# Keyboard.net
KiCad netlist of a schematic drawn in EAGLE
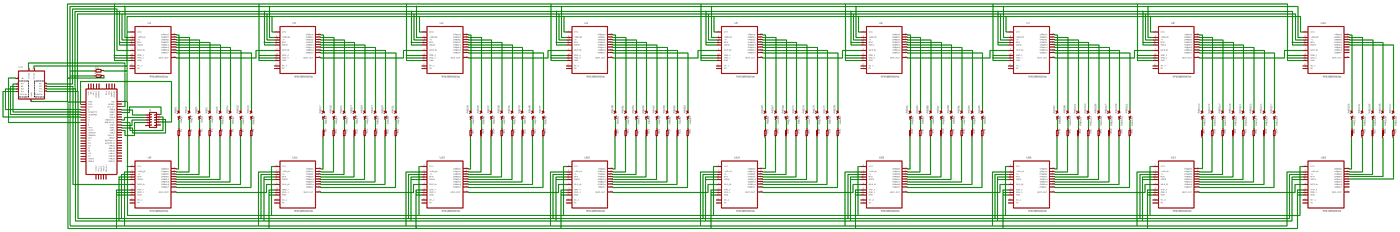
[diagram p0: schematic, sheet 1, overview]
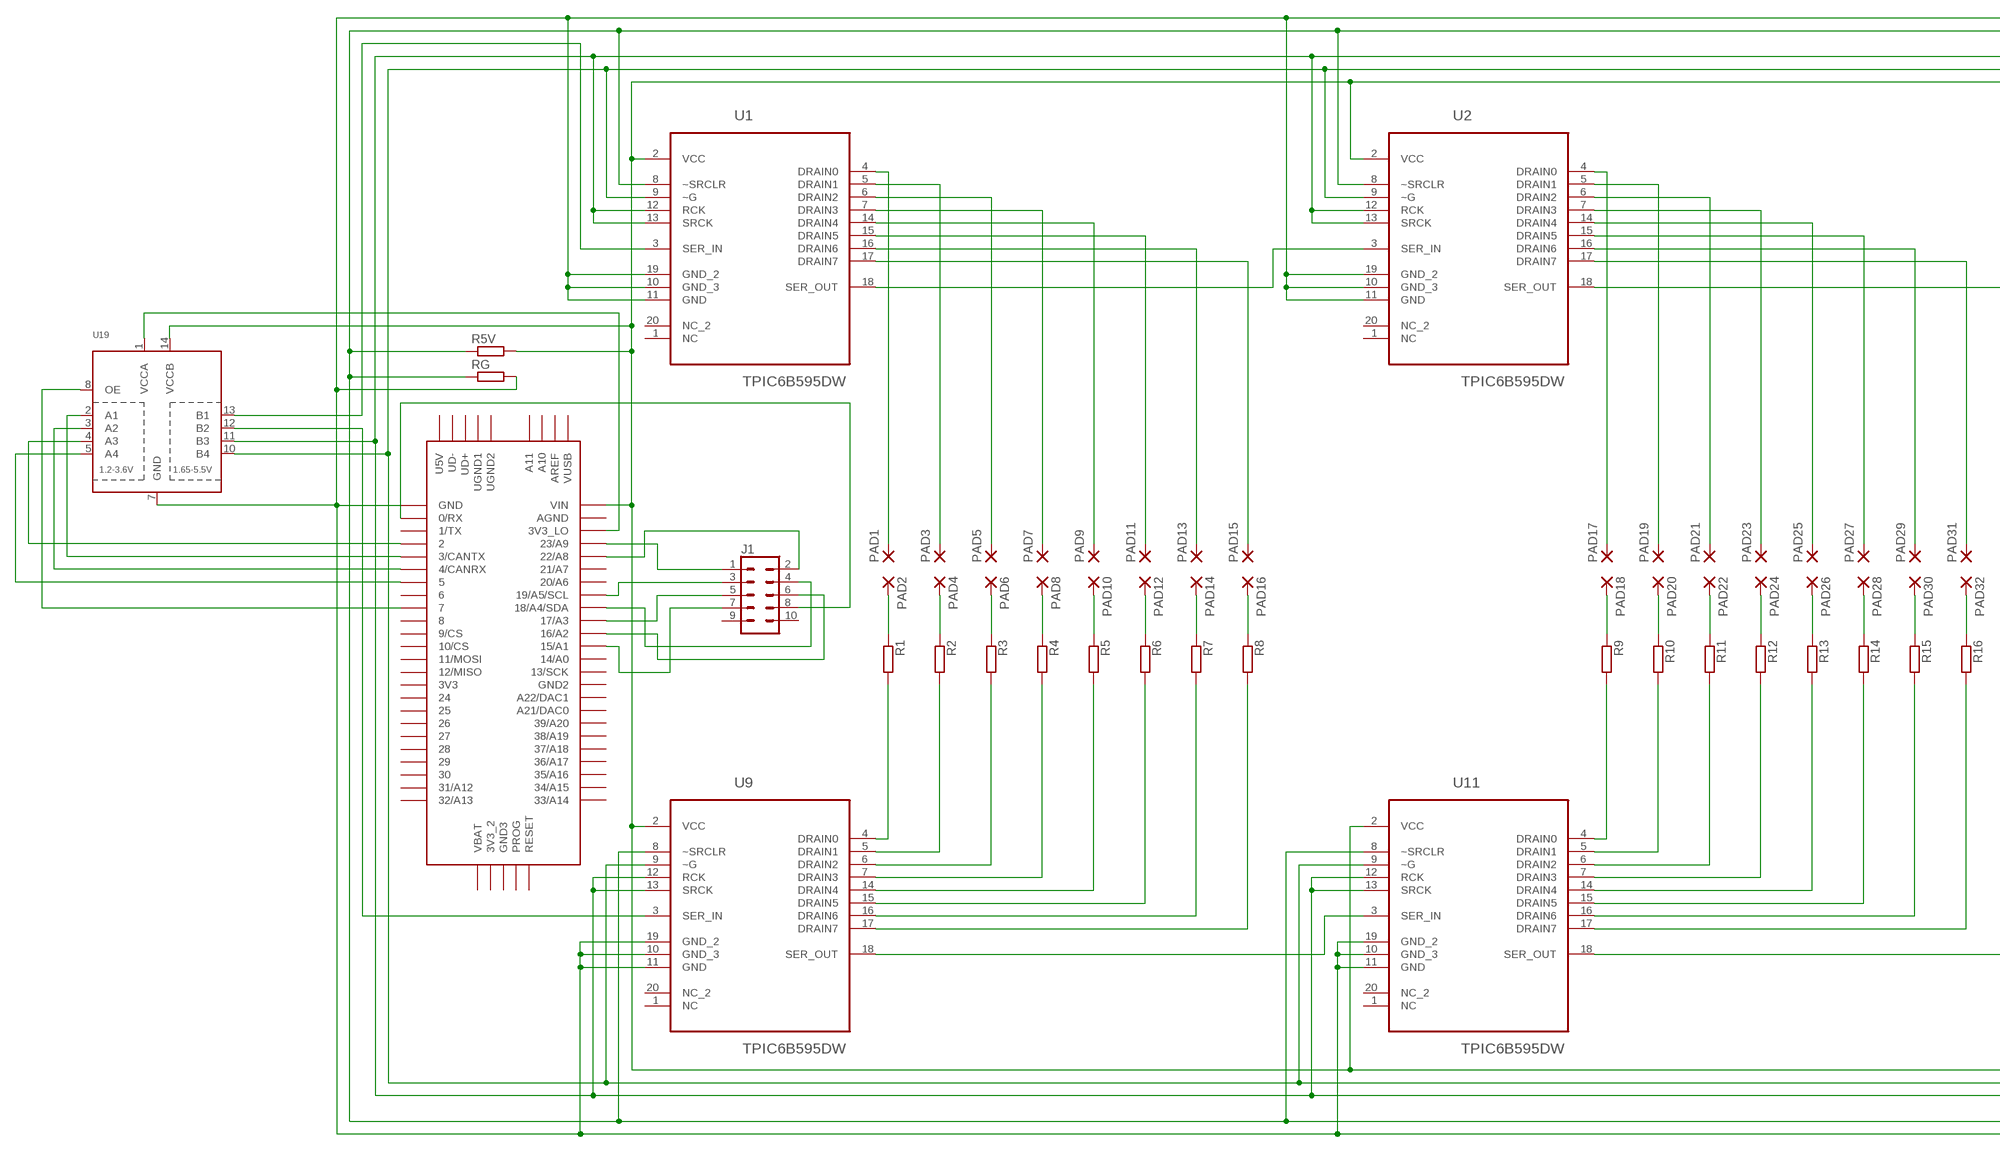
[diagram p1: schematic, sheet 1, part 1 of 4]
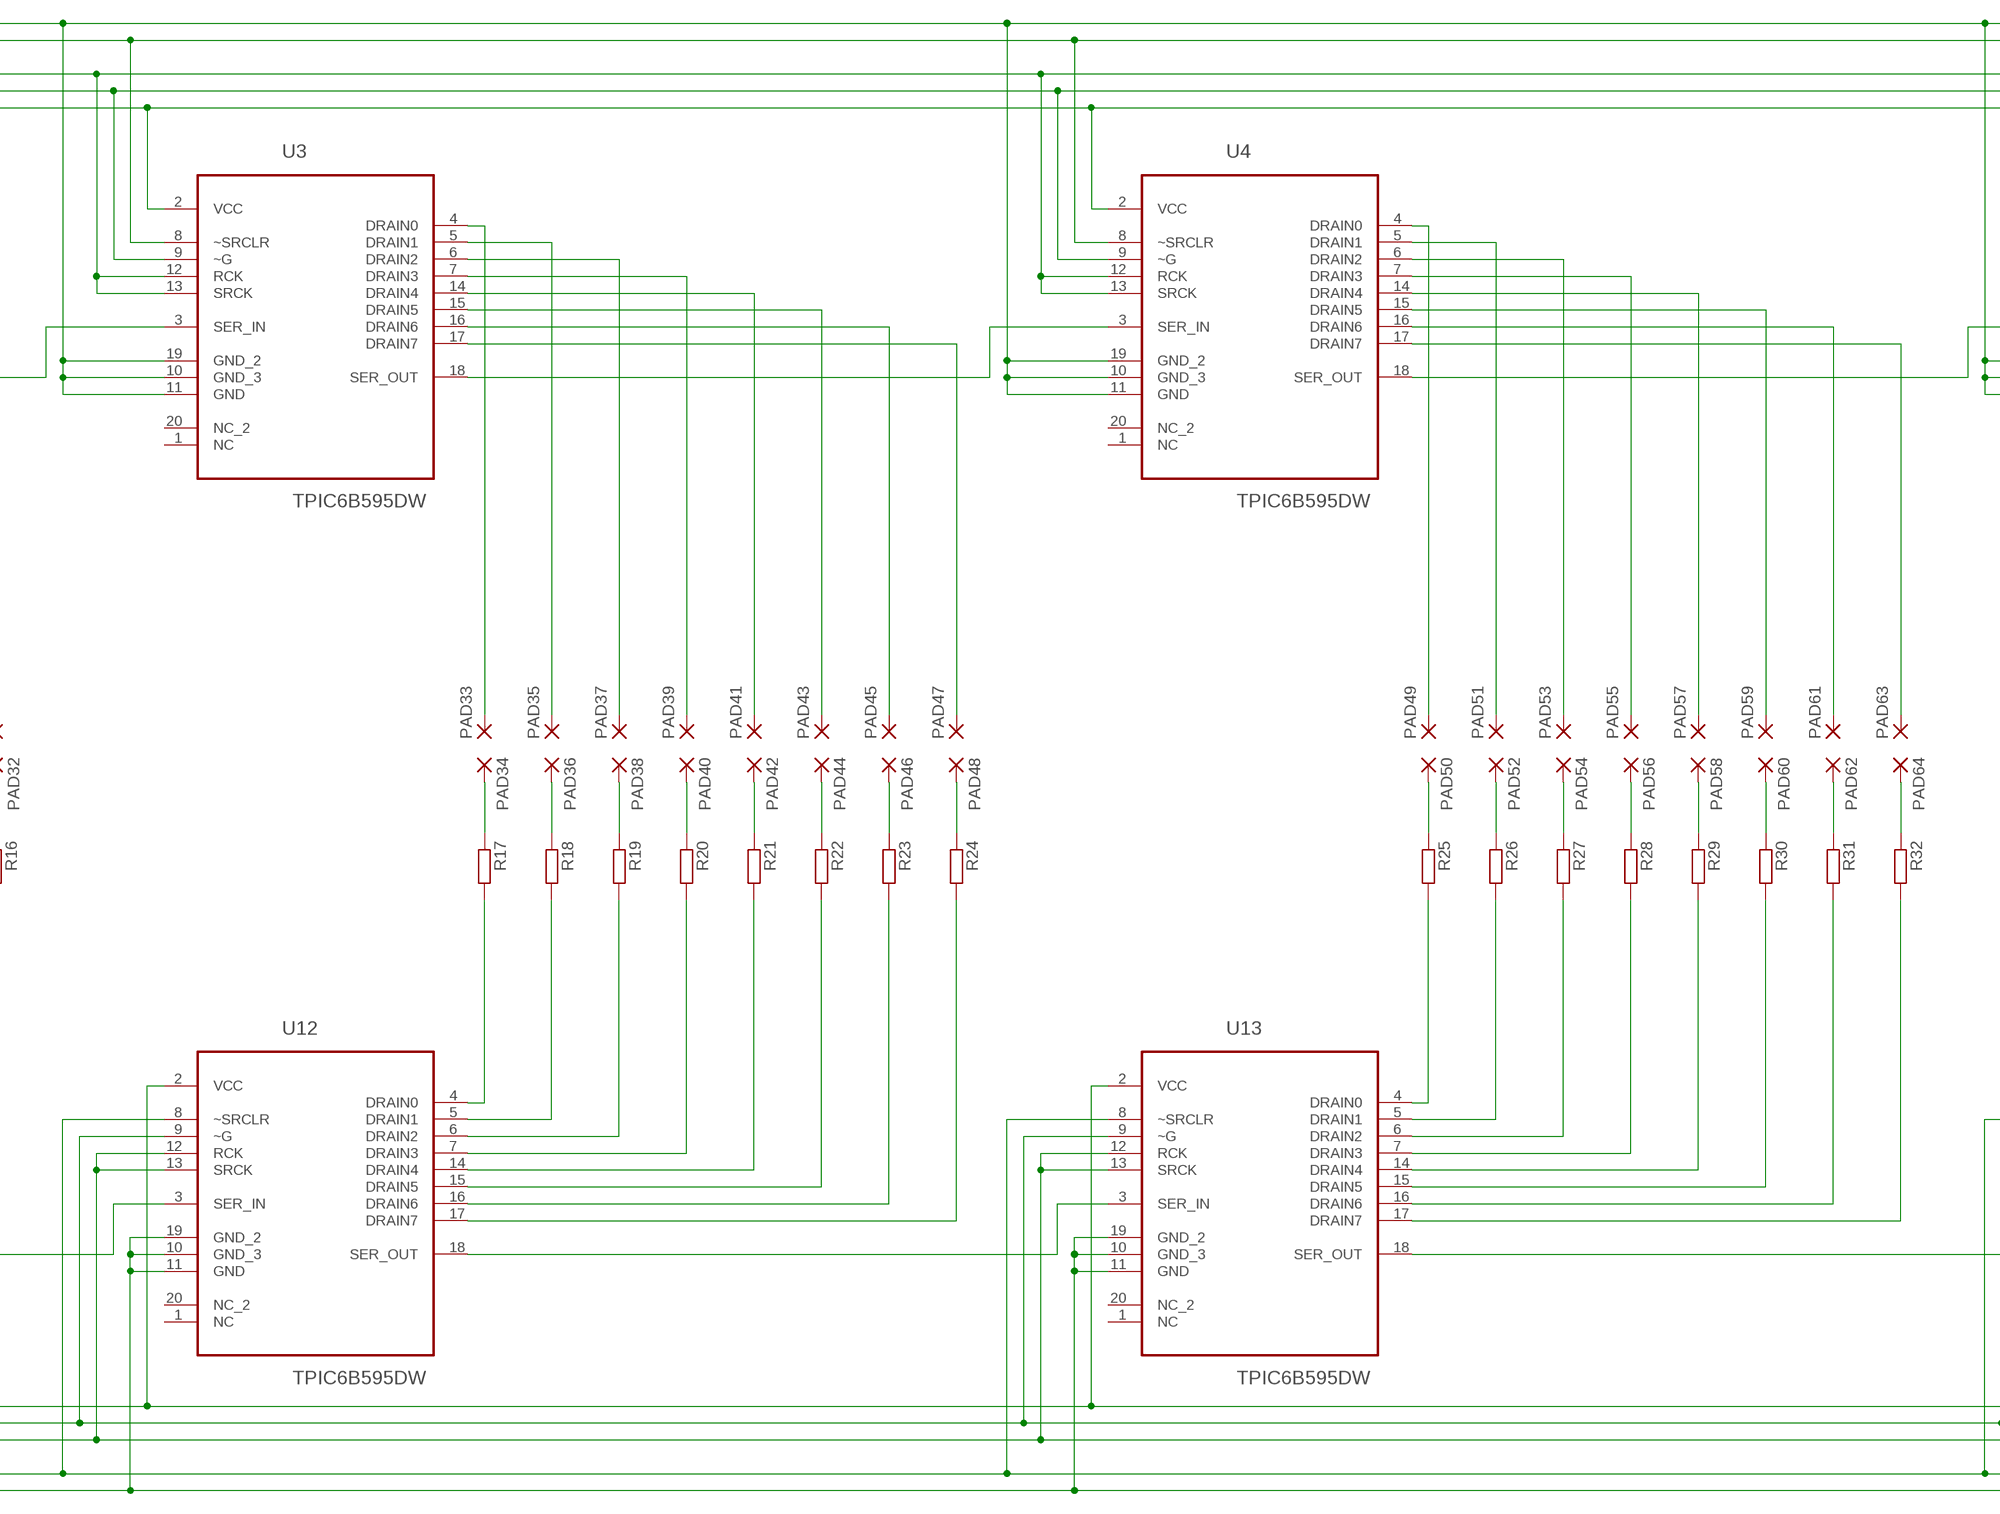
[diagram p2: schematic, sheet 1, part 2 of 4]
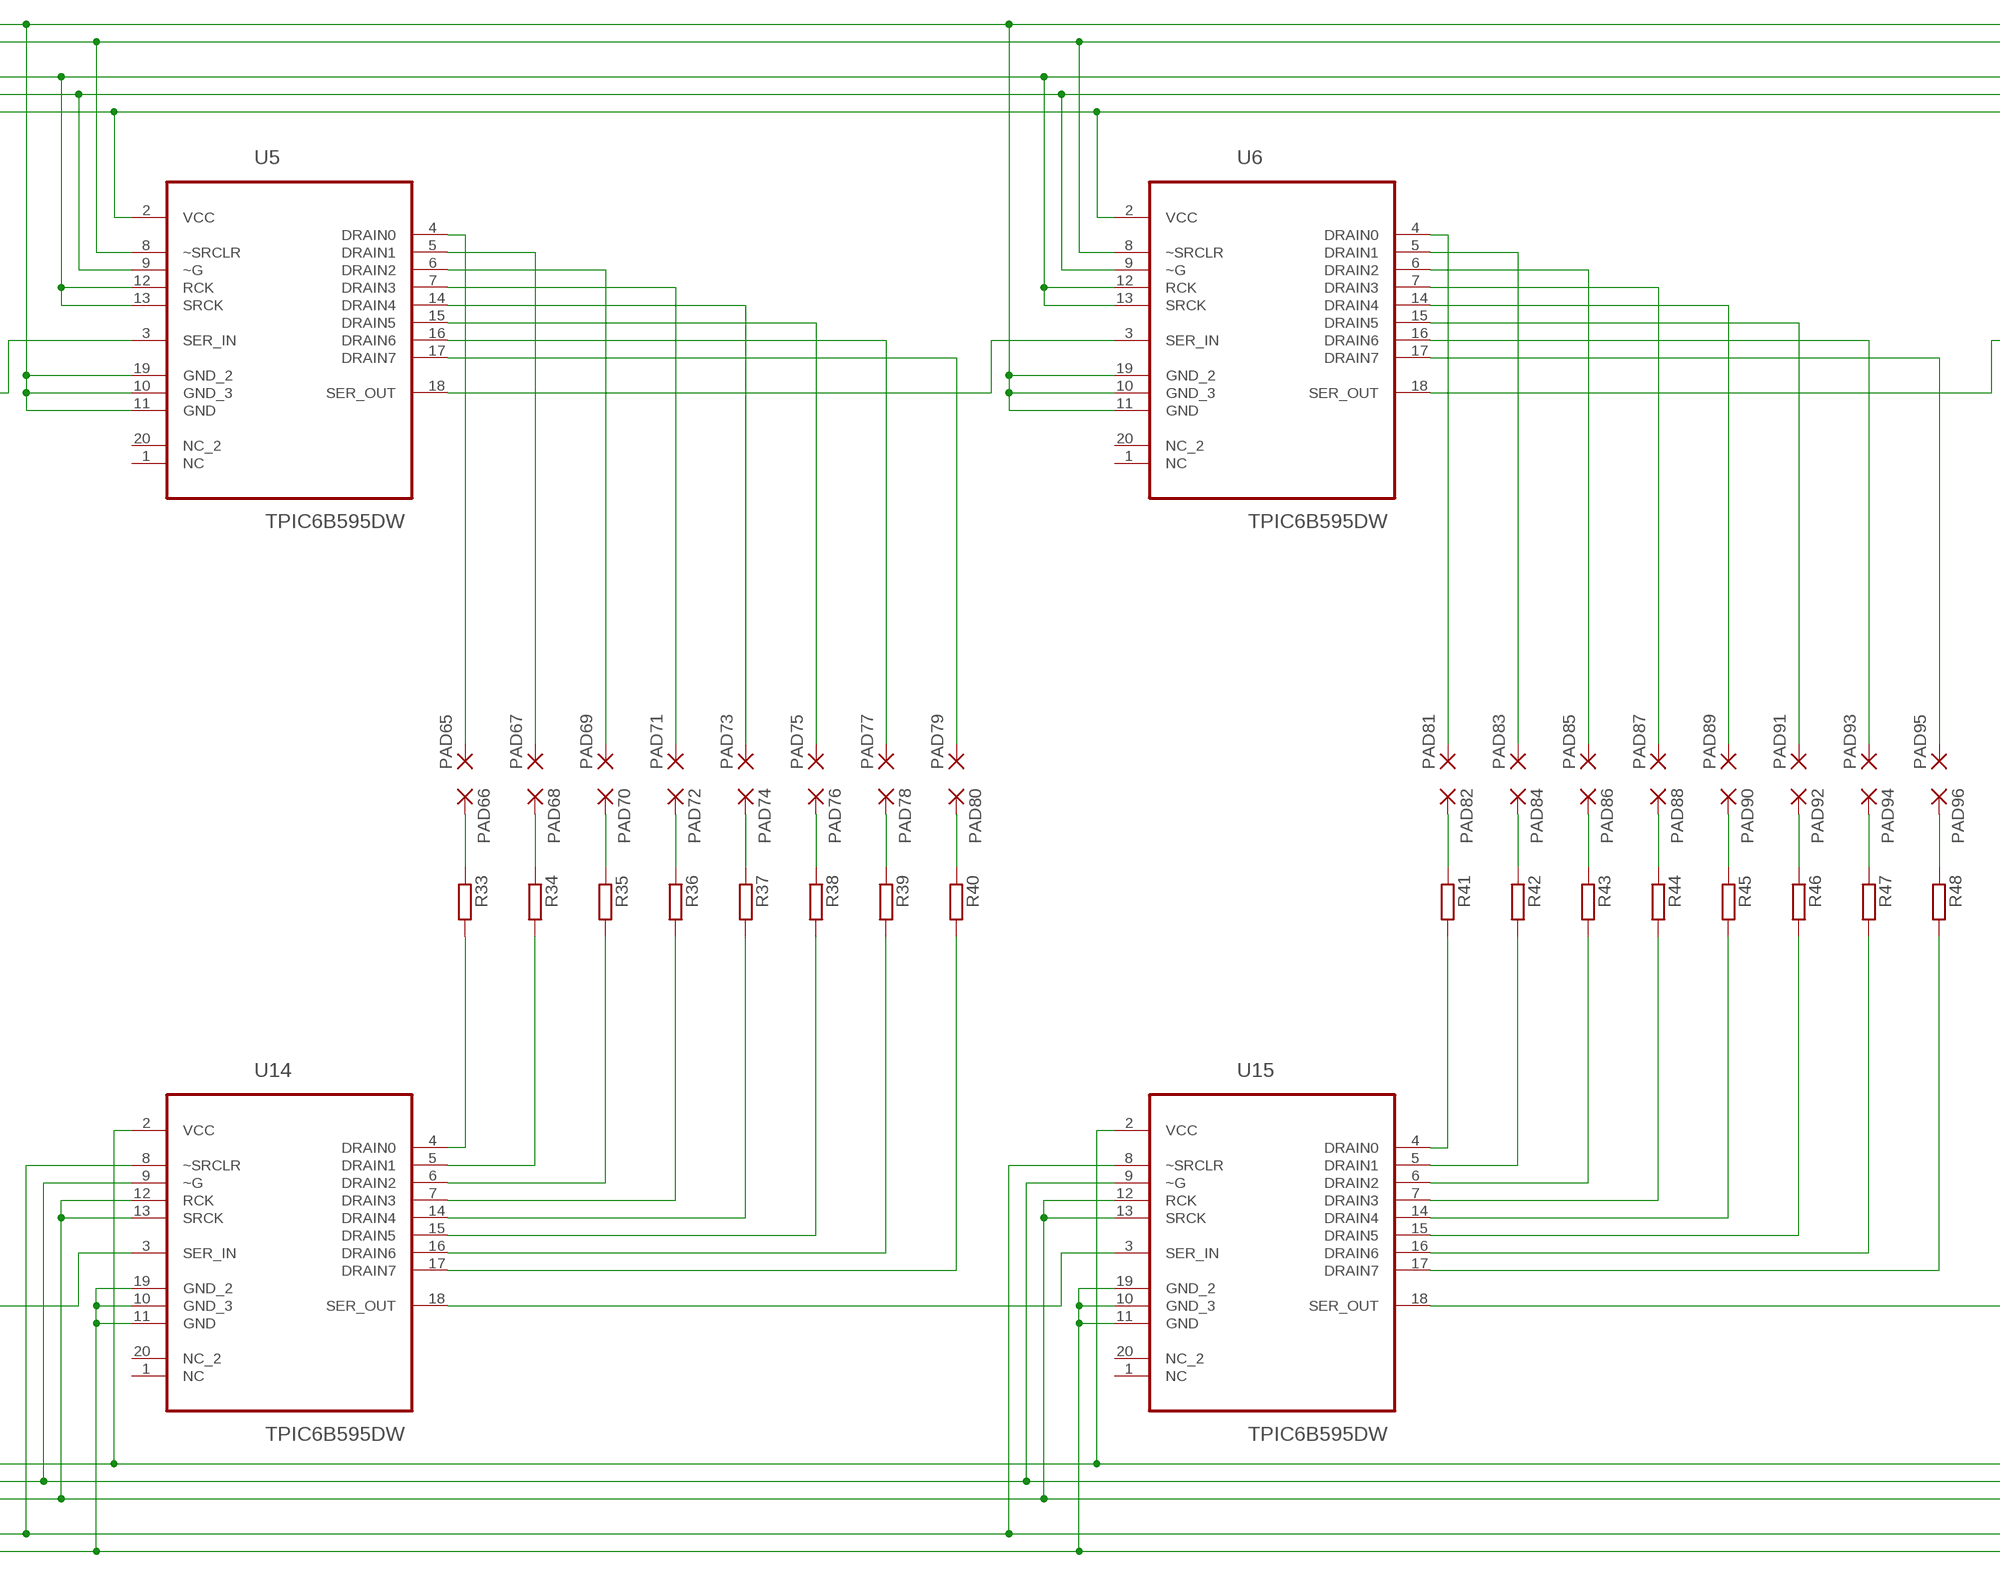
[diagram p3: schematic, sheet 1, part 3 of 4]
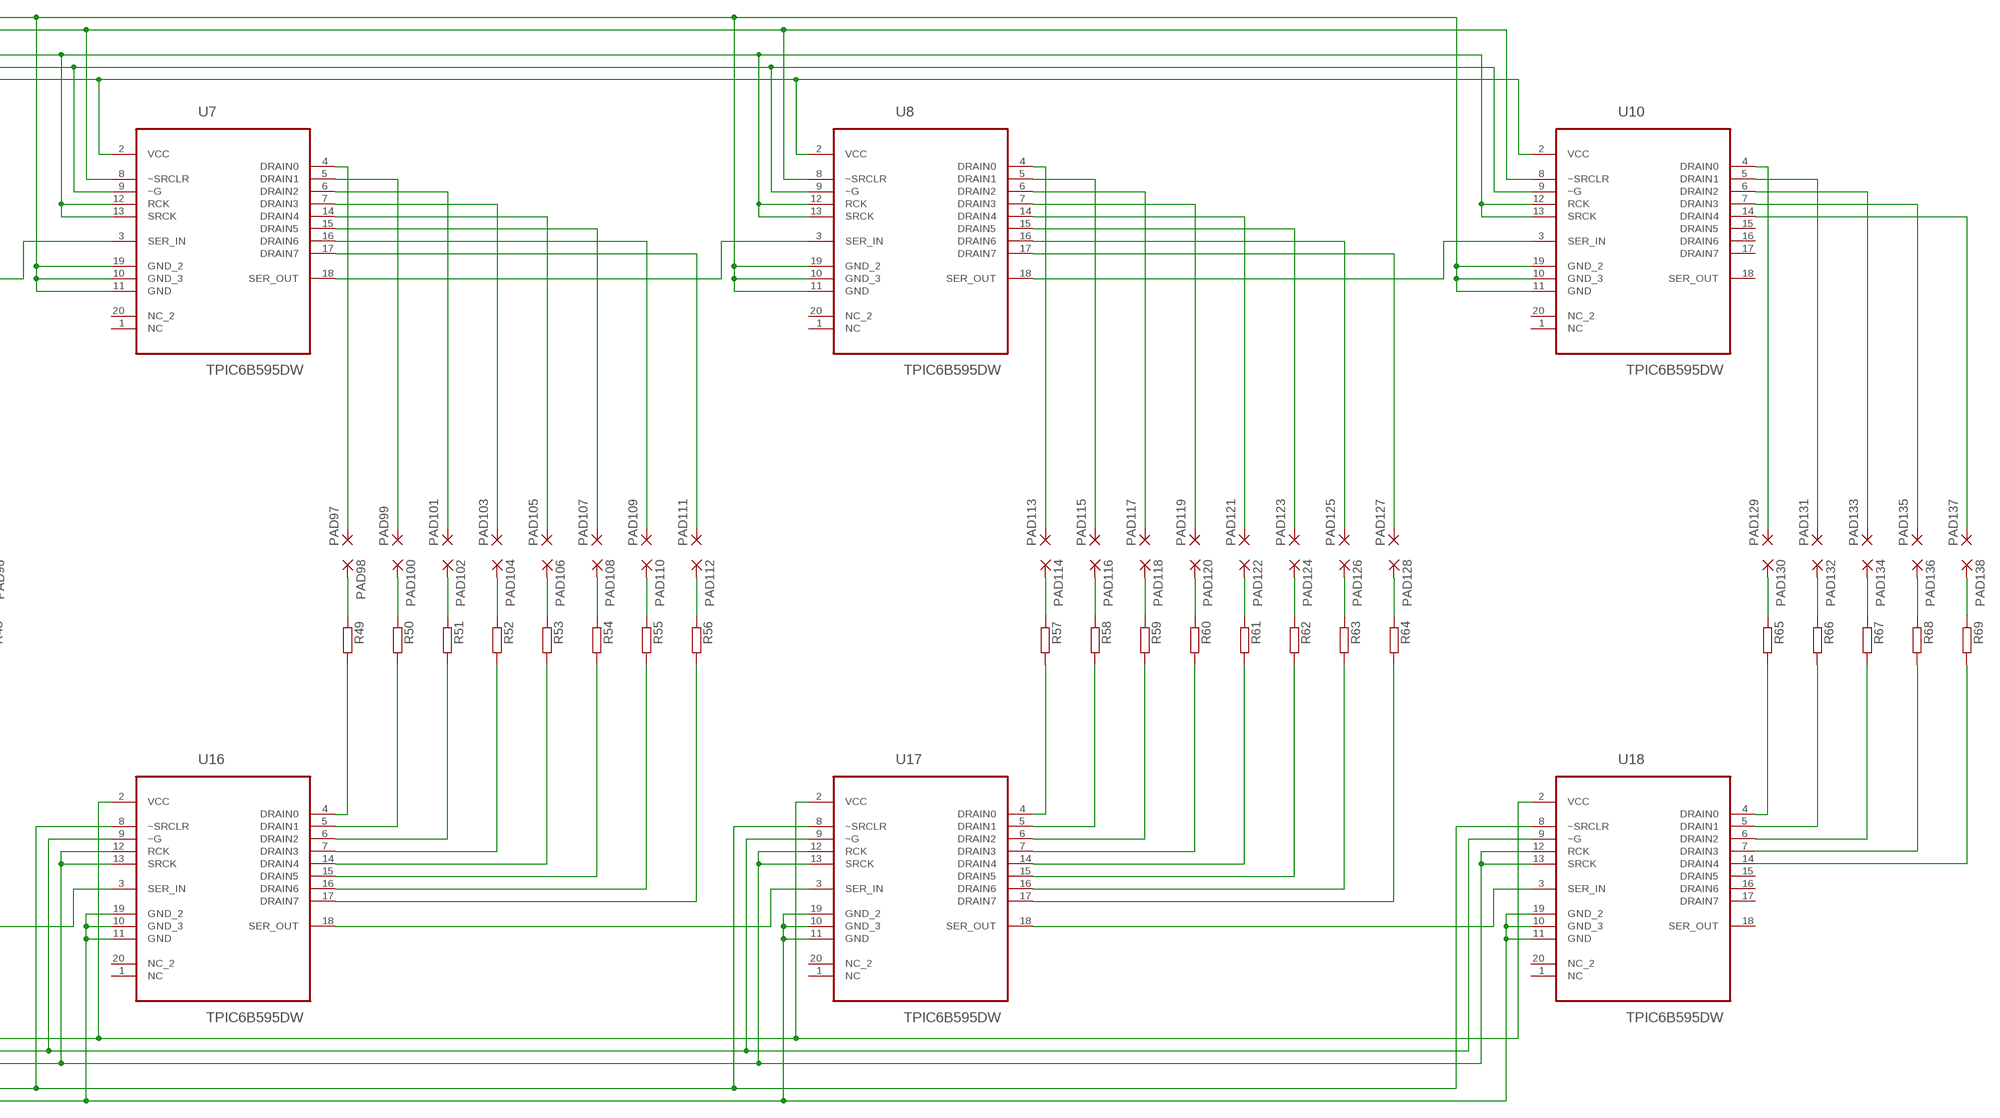
[diagram p4: schematic, sheet 1, part 4 of 4]

(export (version "E")
  (design (tool "Eeschema 10.0.6"))
  (components
    (comp (ref "J1")
      (value "CONN_05X2SHD")
      (footprint "eagle-import:2X5-SHROUDED")
      (libsource (lib "eagle-import") (part "CONN_05X2SHD"))
    )
    (comp (ref "PAD1")
      (value "1,6/0,8")
      (footprint "eagle-import:1,6_0,8")
      (libsource (lib "eagle-import") (part "1,6/0,8"))
    )
    (comp (ref "PAD2")
      (value "1,6/0,8")
      (footprint "eagle-import:1,6_0,8")
      (libsource (lib "eagle-import") (part "1,6/0,8"))
    )
    (comp (ref "PAD3")
      (value "1,6/0,8")
      (footprint "eagle-import:1,6_0,8")
      (libsource (lib "eagle-import") (part "1,6/0,8"))
    )
    (comp (ref "PAD4")
      (value "1,6/0,8")
      (footprint "eagle-import:1,6_0,8")
      (libsource (lib "eagle-import") (part "1,6/0,8"))
    )
    (comp (ref "PAD5")
      (value "1,6/0,8")
      (footprint "eagle-import:1,6_0,8")
      (libsource (lib "eagle-import") (part "1,6/0,8"))
    )
    (comp (ref "PAD6")
      (value "1,6/0,8")
      (footprint "eagle-import:1,6_0,8")
      (libsource (lib "eagle-import") (part "1,6/0,8"))
    )
    (comp (ref "PAD7")
      (value "1,6/0,8")
      (footprint "eagle-import:1,6_0,8")
      (libsource (lib "eagle-import") (part "1,6/0,8"))
    )
    (comp (ref "PAD8")
      (value "1,6/0,8")
      (footprint "eagle-import:1,6_0,8")
      (libsource (lib "eagle-import") (part "1,6/0,8"))
    )
    (comp (ref "PAD9")
      (value "1,6/0,8")
      (footprint "eagle-import:1,6_0,8")
      (libsource (lib "eagle-import") (part "1,6/0,8"))
    )
    (comp (ref "PAD10")
      (value "1,6/0,8")
      (footprint "eagle-import:1,6_0,8")
      (libsource (lib "eagle-import") (part "1,6/0,8"))
    )
    (comp (ref "PAD11")
      (value "1,6/0,8")
      (footprint "eagle-import:1,6_0,8")
      (libsource (lib "eagle-import") (part "1,6/0,8"))
    )
    (comp (ref "PAD12")
      (value "1,6/0,8")
      (footprint "eagle-import:1,6_0,8")
      (libsource (lib "eagle-import") (part "1,6/0,8"))
    )
    (comp (ref "PAD13")
      (value "1,6/0,8")
      (footprint "eagle-import:1,6_0,8")
      (libsource (lib "eagle-import") (part "1,6/0,8"))
    )
    (comp (ref "PAD14")
      (value "1,6/0,8")
      (footprint "eagle-import:1,6_0,8")
      (libsource (lib "eagle-import") (part "1,6/0,8"))
    )
    (comp (ref "PAD15")
      (value "1,6/0,8")
      (footprint "eagle-import:1,6_0,8")
      (libsource (lib "eagle-import") (part "1,6/0,8"))
    )
    (comp (ref "PAD16")
      (value "1,6/0,8")
      (footprint "eagle-import:1,6_0,8")
      (libsource (lib "eagle-import") (part "1,6/0,8"))
    )
    (comp (ref "PAD17")
      (value "1,6/0,8")
      (footprint "eagle-import:1,6_0,8")
      (libsource (lib "eagle-import") (part "1,6/0,8"))
    )
    (comp (ref "PAD18")
      (value "1,6/0,8")
      (footprint "eagle-import:1,6_0,8")
      (libsource (lib "eagle-import") (part "1,6/0,8"))
    )
    (comp (ref "PAD19")
      (value "1,6/0,8")
      (footprint "eagle-import:1,6_0,8")
      (libsource (lib "eagle-import") (part "1,6/0,8"))
    )
    (comp (ref "PAD20")
      (value "1,6/0,8")
      (footprint "eagle-import:1,6_0,8")
      (libsource (lib "eagle-import") (part "1,6/0,8"))
    )
    (comp (ref "PAD21")
      (value "1,6/0,8")
      (footprint "eagle-import:1,6_0,8")
      (libsource (lib "eagle-import") (part "1,6/0,8"))
    )
    (comp (ref "PAD22")
      (value "1,6/0,8")
      (footprint "eagle-import:1,6_0,8")
      (libsource (lib "eagle-import") (part "1,6/0,8"))
    )
    (comp (ref "PAD23")
      (value "1,6/0,8")
      (footprint "eagle-import:1,6_0,8")
      (libsource (lib "eagle-import") (part "1,6/0,8"))
    )
    (comp (ref "PAD24")
      (value "1,6/0,8")
      (footprint "eagle-import:1,6_0,8")
      (libsource (lib "eagle-import") (part "1,6/0,8"))
    )
    (comp (ref "PAD25")
      (value "1,6/0,8")
      (footprint "eagle-import:1,6_0,8")
      (libsource (lib "eagle-import") (part "1,6/0,8"))
    )
    (comp (ref "PAD26")
      (value "1,6/0,8")
      (footprint "eagle-import:1,6_0,8")
      (libsource (lib "eagle-import") (part "1,6/0,8"))
    )
    (comp (ref "PAD27")
      (value "1,6/0,8")
      (footprint "eagle-import:1,6_0,8")
      (libsource (lib "eagle-import") (part "1,6/0,8"))
    )
    (comp (ref "PAD28")
      (value "1,6/0,8")
      (footprint "eagle-import:1,6_0,8")
      (libsource (lib "eagle-import") (part "1,6/0,8"))
    )
    (comp (ref "PAD29")
      (value "1,6/0,8")
      (footprint "eagle-import:1,6_0,8")
      (libsource (lib "eagle-import") (part "1,6/0,8"))
    )
    (comp (ref "PAD30")
      (value "1,6/0,8")
      (footprint "eagle-import:1,6_0,8")
      (libsource (lib "eagle-import") (part "1,6/0,8"))
    )
    (comp (ref "PAD31")
      (value "1,6/0,8")
      (footprint "eagle-import:1,6_0,8")
      (libsource (lib "eagle-import") (part "1,6/0,8"))
    )
    (comp (ref "PAD32")
      (value "1,6/0,8")
      (footprint "eagle-import:1,6_0,8")
      (libsource (lib "eagle-import") (part "1,6/0,8"))
    )
    (comp (ref "PAD33")
      (value "1,6/0,8")
      (footprint "eagle-import:1,6_0,8")
      (libsource (lib "eagle-import") (part "1,6/0,8"))
    )
    (comp (ref "PAD34")
      (value "1,6/0,8")
      (footprint "eagle-import:1,6_0,8")
      (libsource (lib "eagle-import") (part "1,6/0,8"))
    )
    (comp (ref "PAD35")
      (value "1,6/0,8")
      (footprint "eagle-import:1,6_0,8")
      (libsource (lib "eagle-import") (part "1,6/0,8"))
    )
    (comp (ref "PAD36")
      (value "1,6/0,8")
      (footprint "eagle-import:1,6_0,8")
      (libsource (lib "eagle-import") (part "1,6/0,8"))
    )
    (comp (ref "PAD37")
      (value "1,6/0,8")
      (footprint "eagle-import:1,6_0,8")
      (libsource (lib "eagle-import") (part "1,6/0,8"))
    )
    (comp (ref "PAD38")
      (value "1,6/0,8")
      (footprint "eagle-import:1,6_0,8")
      (libsource (lib "eagle-import") (part "1,6/0,8"))
    )
    (comp (ref "PAD39")
      (value "1,6/0,8")
      (footprint "eagle-import:1,6_0,8")
      (libsource (lib "eagle-import") (part "1,6/0,8"))
    )
    (comp (ref "PAD40")
      (value "1,6/0,8")
      (footprint "eagle-import:1,6_0,8")
      (libsource (lib "eagle-import") (part "1,6/0,8"))
    )
    (comp (ref "PAD41")
      (value "1,6/0,8")
      (footprint "eagle-import:1,6_0,8")
      (libsource (lib "eagle-import") (part "1,6/0,8"))
    )
    (comp (ref "PAD42")
      (value "1,6/0,8")
      (footprint "eagle-import:1,6_0,8")
      (libsource (lib "eagle-import") (part "1,6/0,8"))
    )
    (comp (ref "PAD43")
      (value "1,6/0,8")
      (footprint "eagle-import:1,6_0,8")
      (libsource (lib "eagle-import") (part "1,6/0,8"))
    )
    (comp (ref "PAD44")
      (value "1,6/0,8")
      (footprint "eagle-import:1,6_0,8")
      (libsource (lib "eagle-import") (part "1,6/0,8"))
    )
    (comp (ref "PAD45")
      (value "1,6/0,8")
      (footprint "eagle-import:1,6_0,8")
      (libsource (lib "eagle-import") (part "1,6/0,8"))
    )
    (comp (ref "PAD46")
      (value "1,6/0,8")
      (footprint "eagle-import:1,6_0,8")
      (libsource (lib "eagle-import") (part "1,6/0,8"))
    )
    (comp (ref "PAD47")
      (value "1,6/0,8")
      (footprint "eagle-import:1,6_0,8")
      (libsource (lib "eagle-import") (part "1,6/0,8"))
    )
    (comp (ref "PAD48")
      (value "1,6/0,8")
      (footprint "eagle-import:1,6_0,8")
      (libsource (lib "eagle-import") (part "1,6/0,8"))
    )
    (comp (ref "PAD49")
      (value "1,6/0,8")
      (footprint "eagle-import:1,6_0,8")
      (libsource (lib "eagle-import") (part "1,6/0,8"))
    )
    (comp (ref "PAD50")
      (value "1,6/0,8")
      (footprint "eagle-import:1,6_0,8")
      (libsource (lib "eagle-import") (part "1,6/0,8"))
    )
    (comp (ref "PAD51")
      (value "1,6/0,8")
      (footprint "eagle-import:1,6_0,8")
      (libsource (lib "eagle-import") (part "1,6/0,8"))
    )
    (comp (ref "PAD52")
      (value "1,6/0,8")
      (footprint "eagle-import:1,6_0,8")
      (libsource (lib "eagle-import") (part "1,6/0,8"))
    )
    (comp (ref "PAD53")
      (value "1,6/0,8")
      (footprint "eagle-import:1,6_0,8")
      (libsource (lib "eagle-import") (part "1,6/0,8"))
    )
    (comp (ref "PAD54")
      (value "1,6/0,8")
      (footprint "eagle-import:1,6_0,8")
      (libsource (lib "eagle-import") (part "1,6/0,8"))
    )
    (comp (ref "PAD55")
      (value "1,6/0,8")
      (footprint "eagle-import:1,6_0,8")
      (libsource (lib "eagle-import") (part "1,6/0,8"))
    )
    (comp (ref "PAD56")
      (value "1,6/0,8")
      (footprint "eagle-import:1,6_0,8")
      (libsource (lib "eagle-import") (part "1,6/0,8"))
    )
    (comp (ref "PAD57")
      (value "1,6/0,8")
      (footprint "eagle-import:1,6_0,8")
      (libsource (lib "eagle-import") (part "1,6/0,8"))
    )
    (comp (ref "PAD58")
      (value "1,6/0,8")
      (footprint "eagle-import:1,6_0,8")
      (libsource (lib "eagle-import") (part "1,6/0,8"))
    )
    (comp (ref "PAD59")
      (value "1,6/0,8")
      (footprint "eagle-import:1,6_0,8")
      (libsource (lib "eagle-import") (part "1,6/0,8"))
    )
    (comp (ref "PAD60")
      (value "1,6/0,8")
      (footprint "eagle-import:1,6_0,8")
      (libsource (lib "eagle-import") (part "1,6/0,8"))
    )
    (comp (ref "PAD61")
      (value "1,6/0,8")
      (footprint "eagle-import:1,6_0,8")
      (libsource (lib "eagle-import") (part "1,6/0,8"))
    )
    (comp (ref "PAD62")
      (value "1,6/0,8")
      (footprint "eagle-import:1,6_0,8")
      (libsource (lib "eagle-import") (part "1,6/0,8"))
    )
    (comp (ref "PAD63")
      (value "1,6/0,8")
      (footprint "eagle-import:1,6_0,8")
      (libsource (lib "eagle-import") (part "1,6/0,8"))
    )
    (comp (ref "PAD64")
      (value "1,6/0,8")
      (footprint "eagle-import:1,6_0,8")
      (libsource (lib "eagle-import") (part "1,6/0,8"))
    )
    (comp (ref "PAD65")
      (value "1,6/0,8")
      (footprint "eagle-import:1,6_0,8")
      (libsource (lib "eagle-import") (part "1,6/0,8"))
    )
    (comp (ref "PAD66")
      (value "1,6/0,8")
      (footprint "eagle-import:1,6_0,8")
      (libsource (lib "eagle-import") (part "1,6/0,8"))
    )
    (comp (ref "PAD67")
      (value "1,6/0,8")
      (footprint "eagle-import:1,6_0,8")
      (libsource (lib "eagle-import") (part "1,6/0,8"))
    )
    (comp (ref "PAD68")
      (value "1,6/0,8")
      (footprint "eagle-import:1,6_0,8")
      (libsource (lib "eagle-import") (part "1,6/0,8"))
    )
    (comp (ref "PAD69")
      (value "1,6/0,8")
      (footprint "eagle-import:1,6_0,8")
      (libsource (lib "eagle-import") (part "1,6/0,8"))
    )
    (comp (ref "PAD70")
      (value "1,6/0,8")
      (footprint "eagle-import:1,6_0,8")
      (libsource (lib "eagle-import") (part "1,6/0,8"))
    )
    (comp (ref "PAD71")
      (value "1,6/0,8")
      (footprint "eagle-import:1,6_0,8")
      (libsource (lib "eagle-import") (part "1,6/0,8"))
    )
    (comp (ref "PAD72")
      (value "1,6/0,8")
      (footprint "eagle-import:1,6_0,8")
      (libsource (lib "eagle-import") (part "1,6/0,8"))
    )
    (comp (ref "PAD73")
      (value "1,6/0,8")
      (footprint "eagle-import:1,6_0,8")
      (libsource (lib "eagle-import") (part "1,6/0,8"))
    )
    (comp (ref "PAD74")
      (value "1,6/0,8")
      (footprint "eagle-import:1,6_0,8")
      (libsource (lib "eagle-import") (part "1,6/0,8"))
    )
    (comp (ref "PAD75")
      (value "1,6/0,8")
      (footprint "eagle-import:1,6_0,8")
      (libsource (lib "eagle-import") (part "1,6/0,8"))
    )
    (comp (ref "PAD76")
      (value "1,6/0,8")
      (footprint "eagle-import:1,6_0,8")
      (libsource (lib "eagle-import") (part "1,6/0,8"))
    )
    (comp (ref "PAD77")
      (value "1,6/0,8")
      (footprint "eagle-import:1,6_0,8")
      (libsource (lib "eagle-import") (part "1,6/0,8"))
    )
    (comp (ref "PAD78")
      (value "1,6/0,8")
      (footprint "eagle-import:1,6_0,8")
      (libsource (lib "eagle-import") (part "1,6/0,8"))
    )
    (comp (ref "PAD79")
      (value "1,6/0,8")
      (footprint "eagle-import:1,6_0,8")
      (libsource (lib "eagle-import") (part "1,6/0,8"))
    )
    (comp (ref "PAD80")
      (value "1,6/0,8")
      (footprint "eagle-import:1,6_0,8")
      (libsource (lib "eagle-import") (part "1,6/0,8"))
    )
    (comp (ref "PAD81")
      (value "1,6/0,8")
      (footprint "eagle-import:1,6_0,8")
      (libsource (lib "eagle-import") (part "1,6/0,8"))
    )
    (comp (ref "PAD82")
      (value "1,6/0,8")
      (footprint "eagle-import:1,6_0,8")
      (libsource (lib "eagle-import") (part "1,6/0,8"))
    )
    (comp (ref "PAD83")
      (value "1,6/0,8")
      (footprint "eagle-import:1,6_0,8")
      (libsource (lib "eagle-import") (part "1,6/0,8"))
    )
    (comp (ref "PAD84")
      (value "1,6/0,8")
      (footprint "eagle-import:1,6_0,8")
      (libsource (lib "eagle-import") (part "1,6/0,8"))
    )
    (comp (ref "PAD85")
      (value "1,6/0,8")
      (footprint "eagle-import:1,6_0,8")
      (libsource (lib "eagle-import") (part "1,6/0,8"))
    )
    (comp (ref "PAD86")
      (value "1,6/0,8")
      (footprint "eagle-import:1,6_0,8")
      (libsource (lib "eagle-import") (part "1,6/0,8"))
    )
    (comp (ref "PAD87")
      (value "1,6/0,8")
      (footprint "eagle-import:1,6_0,8")
      (libsource (lib "eagle-import") (part "1,6/0,8"))
    )
    (comp (ref "PAD88")
      (value "1,6/0,8")
      (footprint "eagle-import:1,6_0,8")
      (libsource (lib "eagle-import") (part "1,6/0,8"))
    )
    (comp (ref "PAD89")
      (value "1,6/0,8")
      (footprint "eagle-import:1,6_0,8")
      (libsource (lib "eagle-import") (part "1,6/0,8"))
    )
    (comp (ref "PAD90")
      (value "1,6/0,8")
      (footprint "eagle-import:1,6_0,8")
      (libsource (lib "eagle-import") (part "1,6/0,8"))
    )
    (comp (ref "PAD91")
      (value "1,6/0,8")
      (footprint "eagle-import:1,6_0,8")
      (libsource (lib "eagle-import") (part "1,6/0,8"))
    )
    (comp (ref "PAD92")
      (value "1,6/0,8")
      (footprint "eagle-import:1,6_0,8")
      (libsource (lib "eagle-import") (part "1,6/0,8"))
    )
    (comp (ref "PAD93")
      (value "1,6/0,8")
      (footprint "eagle-import:1,6_0,8")
      (libsource (lib "eagle-import") (part "1,6/0,8"))
    )
    (comp (ref "PAD94")
      (value "1,6/0,8")
      (footprint "eagle-import:1,6_0,8")
      (libsource (lib "eagle-import") (part "1,6/0,8"))
    )
    (comp (ref "PAD95")
      (value "1,6/0,8")
      (footprint "eagle-import:1,6_0,8")
      (libsource (lib "eagle-import") (part "1,6/0,8"))
    )
    (comp (ref "PAD96")
      (value "1,6/0,8")
      (footprint "eagle-import:1,6_0,8")
      (libsource (lib "eagle-import") (part "1,6/0,8"))
    )
    (comp (ref "PAD97")
      (value "1,6/0,8")
      (footprint "eagle-import:1,6_0,8")
      (libsource (lib "eagle-import") (part "1,6/0,8"))
    )
    (comp (ref "PAD98")
      (value "1,6/0,8")
      (footprint "eagle-import:1,6_0,8")
      (libsource (lib "eagle-import") (part "1,6/0,8"))
    )
    (comp (ref "PAD99")
      (value "1,6/0,8")
      (footprint "eagle-import:1,6_0,8")
      (libsource (lib "eagle-import") (part "1,6/0,8"))
    )
    (comp (ref "PAD100")
      (value "1,6/0,8")
      (footprint "eagle-import:1,6_0,8")
      (libsource (lib "eagle-import") (part "1,6/0,8"))
    )
    (comp (ref "PAD101")
      (value "1,6/0,8")
      (footprint "eagle-import:1,6_0,8")
      (libsource (lib "eagle-import") (part "1,6/0,8"))
    )
    (comp (ref "PAD102")
      (value "1,6/0,8")
      (footprint "eagle-import:1,6_0,8")
      (libsource (lib "eagle-import") (part "1,6/0,8"))
    )
    (comp (ref "PAD103")
      (value "1,6/0,8")
      (footprint "eagle-import:1,6_0,8")
      (libsource (lib "eagle-import") (part "1,6/0,8"))
    )
    (comp (ref "PAD104")
      (value "1,6/0,8")
      (footprint "eagle-import:1,6_0,8")
      (libsource (lib "eagle-import") (part "1,6/0,8"))
    )
    (comp (ref "PAD105")
      (value "1,6/0,8")
      (footprint "eagle-import:1,6_0,8")
      (libsource (lib "eagle-import") (part "1,6/0,8"))
    )
    (comp (ref "PAD106")
      (value "1,6/0,8")
      (footprint "eagle-import:1,6_0,8")
      (libsource (lib "eagle-import") (part "1,6/0,8"))
    )
    (comp (ref "PAD107")
      (value "1,6/0,8")
      (footprint "eagle-import:1,6_0,8")
      (libsource (lib "eagle-import") (part "1,6/0,8"))
    )
    (comp (ref "PAD108")
      (value "1,6/0,8")
      (footprint "eagle-import:1,6_0,8")
      (libsource (lib "eagle-import") (part "1,6/0,8"))
    )
    (comp (ref "PAD109")
      (value "1,6/0,8")
      (footprint "eagle-import:1,6_0,8")
      (libsource (lib "eagle-import") (part "1,6/0,8"))
    )
    (comp (ref "PAD110")
      (value "1,6/0,8")
      (footprint "eagle-import:1,6_0,8")
      (libsource (lib "eagle-import") (part "1,6/0,8"))
    )
    (comp (ref "PAD111")
      (value "1,6/0,8")
      (footprint "eagle-import:1,6_0,8")
      (libsource (lib "eagle-import") (part "1,6/0,8"))
    )
    (comp (ref "PAD112")
      (value "1,6/0,8")
      (footprint "eagle-import:1,6_0,8")
      (libsource (lib "eagle-import") (part "1,6/0,8"))
    )
    (comp (ref "PAD113")
      (value "1,6/0,8")
      (footprint "eagle-import:1,6_0,8")
      (libsource (lib "eagle-import") (part "1,6/0,8"))
    )
    (comp (ref "PAD114")
      (value "1,6/0,8")
      (footprint "eagle-import:1,6_0,8")
      (libsource (lib "eagle-import") (part "1,6/0,8"))
    )
    (comp (ref "PAD115")
      (value "1,6/0,8")
      (footprint "eagle-import:1,6_0,8")
      (libsource (lib "eagle-import") (part "1,6/0,8"))
    )
    (comp (ref "PAD116")
      (value "1,6/0,8")
      (footprint "eagle-import:1,6_0,8")
      (libsource (lib "eagle-import") (part "1,6/0,8"))
    )
    (comp (ref "PAD117")
      (value "1,6/0,8")
      (footprint "eagle-import:1,6_0,8")
      (libsource (lib "eagle-import") (part "1,6/0,8"))
    )
    (comp (ref "PAD118")
      (value "1,6/0,8")
      (footprint "eagle-import:1,6_0,8")
      (libsource (lib "eagle-import") (part "1,6/0,8"))
    )
    (comp (ref "PAD119")
      (value "1,6/0,8")
      (footprint "eagle-import:1,6_0,8")
      (libsource (lib "eagle-import") (part "1,6/0,8"))
    )
    (comp (ref "PAD120")
      (value "1,6/0,8")
      (footprint "eagle-import:1,6_0,8")
      (libsource (lib "eagle-import") (part "1,6/0,8"))
    )
    (comp (ref "PAD121")
      (value "1,6/0,8")
      (footprint "eagle-import:1,6_0,8")
      (libsource (lib "eagle-import") (part "1,6/0,8"))
    )
    (comp (ref "PAD122")
      (value "1,6/0,8")
      (footprint "eagle-import:1,6_0,8")
      (libsource (lib "eagle-import") (part "1,6/0,8"))
    )
    (comp (ref "PAD123")
      (value "1,6/0,8")
      (footprint "eagle-import:1,6_0,8")
      (libsource (lib "eagle-import") (part "1,6/0,8"))
    )
    (comp (ref "PAD124")
      (value "1,6/0,8")
      (footprint "eagle-import:1,6_0,8")
      (libsource (lib "eagle-import") (part "1,6/0,8"))
    )
    (comp (ref "PAD125")
      (value "1,6/0,8")
      (footprint "eagle-import:1,6_0,8")
      (libsource (lib "eagle-import") (part "1,6/0,8"))
    )
    (comp (ref "PAD126")
      (value "1,6/0,8")
      (footprint "eagle-import:1,6_0,8")
      (libsource (lib "eagle-import") (part "1,6/0,8"))
    )
    (comp (ref "PAD127")
      (value "1,6/0,8")
      (footprint "eagle-import:1,6_0,8")
      (libsource (lib "eagle-import") (part "1,6/0,8"))
    )
    (comp (ref "PAD128")
      (value "1,6/0,8")
      (footprint "eagle-import:1,6_0,8")
      (libsource (lib "eagle-import") (part "1,6/0,8"))
    )
    (comp (ref "PAD129")
      (value "1,6/0,8")
      (footprint "eagle-import:1,6_0,8")
      (libsource (lib "eagle-import") (part "1,6/0,8"))
    )
    (comp (ref "PAD130")
      (value "1,6/0,8")
      (footprint "eagle-import:1,6_0,8")
      (libsource (lib "eagle-import") (part "1,6/0,8"))
    )
    (comp (ref "PAD131")
      (value "1,6/0,8")
      (footprint "eagle-import:1,6_0,8")
      (libsource (lib "eagle-import") (part "1,6/0,8"))
    )
    (comp (ref "PAD132")
      (value "1,6/0,8")
      (footprint "eagle-import:1,6_0,8")
      (libsource (lib "eagle-import") (part "1,6/0,8"))
    )
    (comp (ref "PAD133")
      (value "1,6/0,8")
      (footprint "eagle-import:1,6_0,8")
      (libsource (lib "eagle-import") (part "1,6/0,8"))
    )
    (comp (ref "PAD134")
      (value "1,6/0,8")
      (footprint "eagle-import:1,6_0,8")
      (libsource (lib "eagle-import") (part "1,6/0,8"))
    )
    (comp (ref "PAD135")
      (value "1,6/0,8")
      (footprint "eagle-import:1,6_0,8")
      (libsource (lib "eagle-import") (part "1,6/0,8"))
    )
    (comp (ref "PAD136")
      (value "1,6/0,8")
      (footprint "eagle-import:1,6_0,8")
      (libsource (lib "eagle-import") (part "1,6/0,8"))
    )
    (comp (ref "PAD137")
      (value "1,6/0,8")
      (footprint "eagle-import:1,6_0,8")
      (libsource (lib "eagle-import") (part "1,6/0,8"))
    )
    (comp (ref "PAD138")
      (value "1,6/0,8")
      (footprint "eagle-import:1,6_0,8")
      (libsource (lib "eagle-import") (part "1,6/0,8"))
    )
    (comp (ref "R1") (value "R") (footprint "eagle-import:R0805") (libsource (lib "eagle-import") (part "R")))
    (comp (ref "R2") (value "R") (footprint "eagle-import:R0805") (libsource (lib "eagle-import") (part "R")))
    (comp (ref "R3") (value "R") (footprint "eagle-import:R0805") (libsource (lib "eagle-import") (part "R")))
    (comp (ref "R4") (value "R") (footprint "eagle-import:R0805") (libsource (lib "eagle-import") (part "R")))
    (comp (ref "R5") (value "R") (footprint "eagle-import:R0805") (libsource (lib "eagle-import") (part "R")))
    (comp (ref "R5V")
      (value "R")
      (footprint "eagle-import:R0805")
      (libsource (lib "eagle-import") (part "R"))
    )
    (comp (ref "R6") (value "R") (footprint "eagle-import:R0805") (libsource (lib "eagle-import") (part "R")))
    (comp (ref "R7") (value "R") (footprint "eagle-import:R0805") (libsource (lib "eagle-import") (part "R")))
    (comp (ref "R8") (value "R") (footprint "eagle-import:R0805") (libsource (lib "eagle-import") (part "R")))
    (comp (ref "R9") (value "R") (footprint "eagle-import:R0805") (libsource (lib "eagle-import") (part "R")))
    (comp (ref "R10")
      (value "R")
      (footprint "eagle-import:R0805")
      (libsource (lib "eagle-import") (part "R"))
    )
    (comp (ref "R11")
      (value "R")
      (footprint "eagle-import:R0805")
      (libsource (lib "eagle-import") (part "R"))
    )
    (comp (ref "R12")
      (value "R")
      (footprint "eagle-import:R0805")
      (libsource (lib "eagle-import") (part "R"))
    )
    (comp (ref "R13")
      (value "R")
      (footprint "eagle-import:R0805")
      (libsource (lib "eagle-import") (part "R"))
    )
    (comp (ref "R14")
      (value "R")
      (footprint "eagle-import:R0805")
      (libsource (lib "eagle-import") (part "R"))
    )
    (comp (ref "R15")
      (value "R")
      (footprint "eagle-import:R0805")
      (libsource (lib "eagle-import") (part "R"))
    )
    (comp (ref "R16")
      (value "R")
      (footprint "eagle-import:R0805")
      (libsource (lib "eagle-import") (part "R"))
    )
    (comp (ref "R17")
      (value "R")
      (footprint "eagle-import:R0805")
      (libsource (lib "eagle-import") (part "R"))
    )
    (comp (ref "R18")
      (value "R")
      (footprint "eagle-import:R0805")
      (libsource (lib "eagle-import") (part "R"))
    )
    (comp (ref "R19")
      (value "R")
      (footprint "eagle-import:R0805")
      (libsource (lib "eagle-import") (part "R"))
    )
    (comp (ref "R20")
      (value "R")
      (footprint "eagle-import:R0805")
      (libsource (lib "eagle-import") (part "R"))
    )
    (comp (ref "R21")
      (value "R")
      (footprint "eagle-import:R0805")
      (libsource (lib "eagle-import") (part "R"))
    )
    (comp (ref "R22")
      (value "R")
      (footprint "eagle-import:R0805")
      (libsource (lib "eagle-import") (part "R"))
    )
    (comp (ref "R23")
      (value "R")
      (footprint "eagle-import:R0805")
      (libsource (lib "eagle-import") (part "R"))
    )
    (comp (ref "R24")
      (value "R")
      (footprint "eagle-import:R0805")
      (libsource (lib "eagle-import") (part "R"))
    )
    (comp (ref "R25")
      (value "R")
      (footprint "eagle-import:R0805")
      (libsource (lib "eagle-import") (part "R"))
    )
    (comp (ref "R26")
      (value "R")
      (footprint "eagle-import:R0805")
      (libsource (lib "eagle-import") (part "R"))
    )
    (comp (ref "R27")
      (value "R")
      (footprint "eagle-import:R0805")
      (libsource (lib "eagle-import") (part "R"))
    )
    (comp (ref "R28")
      (value "R")
      (footprint "eagle-import:R0805")
      (libsource (lib "eagle-import") (part "R"))
    )
    (comp (ref "R29")
      (value "R")
      (footprint "eagle-import:R0805")
      (libsource (lib "eagle-import") (part "R"))
    )
    (comp (ref "R30")
      (value "R")
      (footprint "eagle-import:R0805")
      (libsource (lib "eagle-import") (part "R"))
    )
    (comp (ref "R31")
      (value "R")
      (footprint "eagle-import:R0805")
      (libsource (lib "eagle-import") (part "R"))
    )
    (comp (ref "R32")
      (value "R")
      (footprint "eagle-import:R0805")
      (libsource (lib "eagle-import") (part "R"))
    )
    (comp (ref "R33")
      (value "R")
      (footprint "eagle-import:R0805")
      (libsource (lib "eagle-import") (part "R"))
    )
    (comp (ref "R34")
      (value "R")
      (footprint "eagle-import:R0805")
      (libsource (lib "eagle-import") (part "R"))
    )
    (comp (ref "R35")
      (value "R")
      (footprint "eagle-import:R0805")
      (libsource (lib "eagle-import") (part "R"))
    )
    (comp (ref "R36")
      (value "R")
      (footprint "eagle-import:R0805")
      (libsource (lib "eagle-import") (part "R"))
    )
    (comp (ref "R37")
      (value "R")
      (footprint "eagle-import:R0805")
      (libsource (lib "eagle-import") (part "R"))
    )
    (comp (ref "R38")
      (value "R")
      (footprint "eagle-import:R0805")
      (libsource (lib "eagle-import") (part "R"))
    )
    (comp (ref "R39")
      (value "R")
      (footprint "eagle-import:R0805")
      (libsource (lib "eagle-import") (part "R"))
    )
    (comp (ref "R40")
      (value "R")
      (footprint "eagle-import:R0805")
      (libsource (lib "eagle-import") (part "R"))
    )
    (comp (ref "R41")
      (value "R")
      (footprint "eagle-import:R0805")
      (libsource (lib "eagle-import") (part "R"))
    )
    (comp (ref "R42")
      (value "R")
      (footprint "eagle-import:R0805")
      (libsource (lib "eagle-import") (part "R"))
    )
    (comp (ref "R43")
      (value "R")
      (footprint "eagle-import:R0805")
      (libsource (lib "eagle-import") (part "R"))
    )
    (comp (ref "R44")
      (value "R")
      (footprint "eagle-import:R0805")
      (libsource (lib "eagle-import") (part "R"))
    )
    (comp (ref "R45")
      (value "R")
      (footprint "eagle-import:R0805")
      (libsource (lib "eagle-import") (part "R"))
    )
    (comp (ref "R46")
      (value "R")
      (footprint "eagle-import:R0805")
      (libsource (lib "eagle-import") (part "R"))
    )
    (comp (ref "R47")
      (value "R")
      (footprint "eagle-import:R0805")
      (libsource (lib "eagle-import") (part "R"))
    )
    (comp (ref "R48")
      (value "R")
      (footprint "eagle-import:R0805")
      (libsource (lib "eagle-import") (part "R"))
    )
    (comp (ref "R49")
      (value "R")
      (footprint "eagle-import:R0805")
      (libsource (lib "eagle-import") (part "R"))
    )
    (comp (ref "R50")
      (value "R")
      (footprint "eagle-import:R0805")
      (libsource (lib "eagle-import") (part "R"))
    )
    (comp (ref "R51")
      (value "R")
      (footprint "eagle-import:R0805")
      (libsource (lib "eagle-import") (part "R"))
    )
    (comp (ref "R52")
      (value "R")
      (footprint "eagle-import:R0805")
      (libsource (lib "eagle-import") (part "R"))
    )
    (comp (ref "R53")
      (value "R")
      (footprint "eagle-import:R0805")
      (libsource (lib "eagle-import") (part "R"))
    )
    (comp (ref "R54")
      (value "R")
      (footprint "eagle-import:R0805")
      (libsource (lib "eagle-import") (part "R"))
    )
    (comp (ref "R55")
      (value "R")
      (footprint "eagle-import:R0805")
      (libsource (lib "eagle-import") (part "R"))
    )
    (comp (ref "R56")
      (value "R")
      (footprint "eagle-import:R0805")
      (libsource (lib "eagle-import") (part "R"))
    )
    (comp (ref "R57")
      (value "R")
      (footprint "eagle-import:R0805")
      (libsource (lib "eagle-import") (part "R"))
    )
    (comp (ref "R58")
      (value "R")
      (footprint "eagle-import:R0805")
      (libsource (lib "eagle-import") (part "R"))
    )
    (comp (ref "R59")
      (value "R")
      (footprint "eagle-import:R0805")
      (libsource (lib "eagle-import") (part "R"))
    )
    (comp (ref "R60")
      (value "R")
      (footprint "eagle-import:R0805")
      (libsource (lib "eagle-import") (part "R"))
    )
    (comp (ref "R61")
      (value "R")
      (footprint "eagle-import:R0805")
      (libsource (lib "eagle-import") (part "R"))
    )
    (comp (ref "R62")
      (value "R")
      (footprint "eagle-import:R0805")
      (libsource (lib "eagle-import") (part "R"))
    )
    (comp (ref "R63")
      (value "R")
      (footprint "eagle-import:R0805")
      (libsource (lib "eagle-import") (part "R"))
    )
    (comp (ref "R64")
      (value "R")
      (footprint "eagle-import:R0805")
      (libsource (lib "eagle-import") (part "R"))
    )
    (comp (ref "R65")
      (value "R")
      (footprint "eagle-import:R0805")
      (libsource (lib "eagle-import") (part "R"))
    )
    (comp (ref "R66")
      (value "R")
      (footprint "eagle-import:R0805")
      (libsource (lib "eagle-import") (part "R"))
    )
    (comp (ref "R67")
      (value "R")
      (footprint "eagle-import:R0805")
      (libsource (lib "eagle-import") (part "R"))
    )
    (comp (ref "R68")
      (value "R")
      (footprint "eagle-import:R0805")
      (libsource (lib "eagle-import") (part "R"))
    )
    (comp (ref "R69")
      (value "R")
      (footprint "eagle-import:R0805")
      (libsource (lib "eagle-import") (part "R"))
    )
    (comp (ref "RG") (value "R") (footprint "eagle-import:R0805") (libsource (lib "eagle-import") (part "R")))
    (comp (ref "U$59")
      (value "TEENSY_3.5/3.6")
      (footprint "eagle-import:TEENSY_3.5_3.6")
      (libsource (lib "eagle-import") (part "TEENSY_3.5/3.6"))
    )
    (comp (ref "U1")
      (value "TPIC6B595DW")
      (footprint "eagle-import:SOIC127P1030X265-20N")
      (libsource (lib "eagle-import") (part "TPIC6B595DW"))
    )
    (comp (ref "U2")
      (value "TPIC6B595DW")
      (footprint "eagle-import:SOIC127P1030X265-20N")
      (libsource (lib "eagle-import") (part "TPIC6B595DW"))
    )
    (comp (ref "U3")
      (value "TPIC6B595DW")
      (footprint "eagle-import:SOIC127P1030X265-20N")
      (libsource (lib "eagle-import") (part "TPIC6B595DW"))
    )
    (comp (ref "U4")
      (value "TPIC6B595DW")
      (footprint "eagle-import:SOIC127P1030X265-20N")
      (libsource (lib "eagle-import") (part "TPIC6B595DW"))
    )
    (comp (ref "U5")
      (value "TPIC6B595DW")
      (footprint "eagle-import:SOIC127P1030X265-20N")
      (libsource (lib "eagle-import") (part "TPIC6B595DW"))
    )
    (comp (ref "U6")
      (value "TPIC6B595DW")
      (footprint "eagle-import:SOIC127P1030X265-20N")
      (libsource (lib "eagle-import") (part "TPIC6B595DW"))
    )
    (comp (ref "U7")
      (value "TPIC6B595DW")
      (footprint "eagle-import:SOIC127P1030X265-20N")
      (libsource (lib "eagle-import") (part "TPIC6B595DW"))
    )
    (comp (ref "U8")
      (value "TPIC6B595DW")
      (footprint "eagle-import:SOIC127P1030X265-20N")
      (libsource (lib "eagle-import") (part "TPIC6B595DW"))
    )
    (comp (ref "U9")
      (value "TPIC6B595DW")
      (footprint "eagle-import:SOIC127P1030X265-20N")
      (libsource (lib "eagle-import") (part "TPIC6B595DW"))
    )
    (comp (ref "U10")
      (value "TPIC6B595DW")
      (footprint "eagle-import:SOIC127P1030X265-20N")
      (libsource (lib "eagle-import") (part "TPIC6B595DW"))
    )
    (comp (ref "U11")
      (value "TPIC6B595DW")
      (footprint "eagle-import:SOIC127P1030X265-20N")
      (libsource (lib "eagle-import") (part "TPIC6B595DW"))
    )
    (comp (ref "U12")
      (value "TPIC6B595DW")
      (footprint "eagle-import:SOIC127P1030X265-20N")
      (libsource (lib "eagle-import") (part "TPIC6B595DW"))
    )
    (comp (ref "U13")
      (value "TPIC6B595DW")
      (footprint "eagle-import:SOIC127P1030X265-20N")
      (libsource (lib "eagle-import") (part "TPIC6B595DW"))
    )
    (comp (ref "U14")
      (value "TPIC6B595DW")
      (footprint "eagle-import:SOIC127P1030X265-20N")
      (libsource (lib "eagle-import") (part "TPIC6B595DW"))
    )
    (comp (ref "U15")
      (value "TPIC6B595DW")
      (footprint "eagle-import:SOIC127P1030X265-20N")
      (libsource (lib "eagle-import") (part "TPIC6B595DW"))
    )
    (comp (ref "U16")
      (value "TPIC6B595DW")
      (footprint "eagle-import:SOIC127P1030X265-20N")
      (libsource (lib "eagle-import") (part "TPIC6B595DW"))
    )
    (comp (ref "U17")
      (value "TPIC6B595DW")
      (footprint "eagle-import:SOIC127P1030X265-20N")
      (libsource (lib "eagle-import") (part "TPIC6B595DW"))
    )
    (comp (ref "U18")
      (value "TPIC6B595DW")
      (footprint "eagle-import:SOIC127P1030X265-20N")
      (libsource (lib "eagle-import") (part "TPIC6B595DW"))
    )
    (comp (ref "U19")
      (value "TXB0104PWRSOIC14")
      (footprint "eagle-import:SO14")
      (libsource (lib "eagle-import") (part "TXB0104PWRSOIC14"))
    )
  )
  (nets
    (net (code "1") (name "Net-(J1-Pad1)") (class "Default")
      (node (ref "J1") (pin "1") (pinfunction "1_1") (pintype "passive"))
      (node (ref "U$59") (pin "23/A9") (pinfunction "23/A9_23/A9") (pintype "bidirectional"))
    )
    (net (code "2") (name "Net-(J1-Pad2)") (class "Default")
      (node (ref "J1") (pin "2") (pinfunction "2_2") (pintype "passive"))
      (node (ref "U$59") (pin "22/A8") (pinfunction "22/A8_22/A8") (pintype "bidirectional"))
    )
    (net (code "3") (name "Net-(J1-Pad3)") (class "Default")
      (node (ref "J1") (pin "3") (pinfunction "3_3") (pintype "passive"))
      (node (ref "U$59") (pin "19/A5/SCL") (pinfunction "19/A5/SCL_19/A5/SCL") (pintype "bidirectional"))
    )
    (net (code "4") (name "Net-(J1-Pad4)") (class "Default")
      (node (ref "J1") (pin "4") (pinfunction "4_4") (pintype "passive"))
      (node (ref "U$59") (pin "18/A4/SDA") (pinfunction "18/A4/SDA_18/A4/SDA") (pintype "bidirectional"))
    )
    (net (code "5") (name "Net-(J1-Pad5)") (class "Default")
      (node (ref "J1") (pin "5") (pinfunction "5_5") (pintype "passive"))
      (node (ref "U$59") (pin "17/A3") (pinfunction "17/A3_17/A3") (pintype "bidirectional"))
    )
    (net (code "6") (name "Net-(J1-Pad6)") (class "Default")
      (node (ref "J1") (pin "6") (pinfunction "6_6") (pintype "passive"))
      (node (ref "U$59") (pin "16/A2") (pinfunction "16/A2_16/A2") (pintype "bidirectional"))
    )
    (net (code "7") (name "Net-(J1-Pad7)") (class "Default")
      (node (ref "J1") (pin "7") (pinfunction "7_7") (pintype "passive"))
      (node (ref "U$59") (pin "15/A1") (pinfunction "15/A1_15/A1") (pintype "bidirectional"))
    )
    (net (code "8") (name "Net-(J1-Pad8)") (class "Default")
      (node (ref "J1") (pin "8") (pinfunction "8_8") (pintype "passive"))
      (node (ref "U$59") (pin "0/RX") (pinfunction "0/RX_0/RX") (pintype "bidirectional"))
    )
    (net (code "9") (name "Net-(PAD1-P)") (class "Default")
      (node (ref "PAD1") (pin "1") (pinfunction "P_1") (pintype "passive"))
      (node (ref "U1") (pin "4") (pinfunction "DRAIN0_4") (pintype "output"))
    )
    (net (code "10") (name "Net-(PAD2-P)") (class "Default")
      (node (ref "PAD2") (pin "1") (pinfunction "P_1") (pintype "passive"))
      (node (ref "R1") (pin "1") (pinfunction "1_1") (pintype "passive"))
    )
    (net (code "11") (name "Net-(PAD3-P)") (class "Default")
      (node (ref "PAD3") (pin "1") (pinfunction "P_1") (pintype "passive"))
      (node (ref "U1") (pin "5") (pinfunction "DRAIN1_5") (pintype "output"))
    )
    (net (code "12") (name "Net-(PAD4-P)") (class "Default")
      (node (ref "PAD4") (pin "1") (pinfunction "P_1") (pintype "passive"))
      (node (ref "R2") (pin "1") (pinfunction "1_1") (pintype "passive"))
    )
    (net (code "13") (name "Net-(PAD5-P)") (class "Default")
      (node (ref "PAD5") (pin "1") (pinfunction "P_1") (pintype "passive"))
      (node (ref "U1") (pin "6") (pinfunction "DRAIN2_6") (pintype "output"))
    )
    (net (code "14") (name "Net-(PAD6-P)") (class "Default")
      (node (ref "PAD6") (pin "1") (pinfunction "P_1") (pintype "passive"))
      (node (ref "R3") (pin "1") (pinfunction "1_1") (pintype "passive"))
    )
    (net (code "15") (name "Net-(PAD7-P)") (class "Default")
      (node (ref "PAD7") (pin "1") (pinfunction "P_1") (pintype "passive"))
      (node (ref "U1") (pin "7") (pinfunction "DRAIN3_7") (pintype "output"))
    )
    (net (code "16") (name "Net-(PAD8-P)") (class "Default")
      (node (ref "PAD8") (pin "1") (pinfunction "P_1") (pintype "passive"))
      (node (ref "R4") (pin "1") (pinfunction "1_1") (pintype "passive"))
    )
    (net (code "17") (name "Net-(PAD9-P)") (class "Default")
      (node (ref "PAD9") (pin "1") (pinfunction "P_1") (pintype "passive"))
      (node (ref "U1") (pin "14") (pinfunction "DRAIN4_14") (pintype "output"))
    )
    (net (code "18") (name "Net-(PAD10-P)") (class "Default")
      (node (ref "PAD10") (pin "1") (pinfunction "P_1") (pintype "passive"))
      (node (ref "R5") (pin "1") (pinfunction "1_1") (pintype "passive"))
    )
    (net (code "19") (name "Net-(PAD11-P)") (class "Default")
      (node (ref "PAD11") (pin "1") (pinfunction "P_1") (pintype "passive"))
      (node (ref "U1") (pin "15") (pinfunction "DRAIN5_15") (pintype "output"))
    )
    (net (code "20") (name "Net-(PAD12-P)") (class "Default")
      (node (ref "PAD12") (pin "1") (pinfunction "P_1") (pintype "passive"))
      (node (ref "R6") (pin "1") (pinfunction "1_1") (pintype "passive"))
    )
    (net (code "21") (name "Net-(PAD13-P)") (class "Default")
      (node (ref "PAD13") (pin "1") (pinfunction "P_1") (pintype "passive"))
      (node (ref "U1") (pin "16") (pinfunction "DRAIN6_16") (pintype "output"))
    )
    (net (code "22") (name "Net-(PAD14-P)") (class "Default")
      (node (ref "PAD14") (pin "1") (pinfunction "P_1") (pintype "passive"))
      (node (ref "R7") (pin "1") (pinfunction "1_1") (pintype "passive"))
    )
    (net (code "23") (name "Net-(PAD15-P)") (class "Default")
      (node (ref "PAD15") (pin "1") (pinfunction "P_1") (pintype "passive"))
      (node (ref "U1") (pin "17") (pinfunction "DRAIN7_17") (pintype "output"))
    )
    (net (code "24") (name "Net-(PAD16-P)") (class "Default")
      (node (ref "PAD16") (pin "1") (pinfunction "P_1") (pintype "passive"))
      (node (ref "R8") (pin "1") (pinfunction "1_1") (pintype "passive"))
    )
    (net (code "25") (name "Net-(PAD17-P)") (class "Default")
      (node (ref "PAD17") (pin "1") (pinfunction "P_1") (pintype "passive"))
      (node (ref "U2") (pin "4") (pinfunction "DRAIN0_4") (pintype "output"))
    )
    (net (code "26") (name "Net-(PAD18-P)") (class "Default")
      (node (ref "PAD18") (pin "1") (pinfunction "P_1") (pintype "passive"))
      (node (ref "R9") (pin "1") (pinfunction "1_1") (pintype "passive"))
    )
    (net (code "27") (name "Net-(PAD19-P)") (class "Default")
      (node (ref "PAD19") (pin "1") (pinfunction "P_1") (pintype "passive"))
      (node (ref "U2") (pin "5") (pinfunction "DRAIN1_5") (pintype "output"))
    )
    (net (code "28") (name "Net-(PAD20-P)") (class "Default")
      (node (ref "PAD20") (pin "1") (pinfunction "P_1") (pintype "passive"))
      (node (ref "R10") (pin "1") (pinfunction "1_1") (pintype "passive"))
    )
    (net (code "29") (name "Net-(PAD21-P)") (class "Default")
      (node (ref "PAD21") (pin "1") (pinfunction "P_1") (pintype "passive"))
      (node (ref "U2") (pin "6") (pinfunction "DRAIN2_6") (pintype "output"))
    )
    (net (code "30") (name "Net-(PAD22-P)") (class "Default")
      (node (ref "PAD22") (pin "1") (pinfunction "P_1") (pintype "passive"))
      (node (ref "R11") (pin "1") (pinfunction "1_1") (pintype "passive"))
    )
    (net (code "31") (name "Net-(PAD23-P)") (class "Default")
      (node (ref "PAD23") (pin "1") (pinfunction "P_1") (pintype "passive"))
      (node (ref "U2") (pin "7") (pinfunction "DRAIN3_7") (pintype "output"))
    )
    (net (code "32") (name "Net-(PAD24-P)") (class "Default")
      (node (ref "PAD24") (pin "1") (pinfunction "P_1") (pintype "passive"))
      (node (ref "R12") (pin "1") (pinfunction "1_1") (pintype "passive"))
    )
    (net (code "33") (name "Net-(PAD25-P)") (class "Default")
      (node (ref "PAD25") (pin "1") (pinfunction "P_1") (pintype "passive"))
      (node (ref "U2") (pin "14") (pinfunction "DRAIN4_14") (pintype "output"))
    )
    (net (code "34") (name "Net-(PAD26-P)") (class "Default")
      (node (ref "PAD26") (pin "1") (pinfunction "P_1") (pintype "passive"))
      (node (ref "R13") (pin "1") (pinfunction "1_1") (pintype "passive"))
    )
    (net (code "35") (name "Net-(PAD27-P)") (class "Default")
      (node (ref "PAD27") (pin "1") (pinfunction "P_1") (pintype "passive"))
      (node (ref "U2") (pin "15") (pinfunction "DRAIN5_15") (pintype "output"))
    )
    (net (code "36") (name "Net-(PAD28-P)") (class "Default")
      (node (ref "PAD28") (pin "1") (pinfunction "P_1") (pintype "passive"))
      (node (ref "R14") (pin "1") (pinfunction "1_1") (pintype "passive"))
    )
    (net (code "37") (name "Net-(PAD29-P)") (class "Default")
      (node (ref "PAD29") (pin "1") (pinfunction "P_1") (pintype "passive"))
      (node (ref "U2") (pin "16") (pinfunction "DRAIN6_16") (pintype "output"))
    )
    (net (code "38") (name "Net-(PAD30-P)") (class "Default")
      (node (ref "PAD30") (pin "1") (pinfunction "P_1") (pintype "passive"))
      (node (ref "R15") (pin "1") (pinfunction "1_1") (pintype "passive"))
    )
    (net (code "39") (name "Net-(PAD31-P)") (class "Default")
      (node (ref "PAD31") (pin "1") (pinfunction "P_1") (pintype "passive"))
      (node (ref "U2") (pin "17") (pinfunction "DRAIN7_17") (pintype "output"))
    )
    (net (code "40") (name "Net-(PAD32-P)") (class "Default")
      (node (ref "PAD32") (pin "1") (pinfunction "P_1") (pintype "passive"))
      (node (ref "R16") (pin "1") (pinfunction "1_1") (pintype "passive"))
    )
    (net (code "41") (name "Net-(PAD33-P)") (class "Default")
      (node (ref "PAD33") (pin "1") (pinfunction "P_1") (pintype "passive"))
      (node (ref "U3") (pin "4") (pinfunction "DRAIN0_4") (pintype "output"))
    )
    (net (code "42") (name "Net-(PAD34-P)") (class "Default")
      (node (ref "PAD34") (pin "1") (pinfunction "P_1") (pintype "passive"))
      (node (ref "R17") (pin "1") (pinfunction "1_1") (pintype "passive"))
    )
    (net (code "43") (name "Net-(PAD35-P)") (class "Default")
      (node (ref "PAD35") (pin "1") (pinfunction "P_1") (pintype "passive"))
      (node (ref "U3") (pin "5") (pinfunction "DRAIN1_5") (pintype "output"))
    )
    (net (code "44") (name "Net-(PAD36-P)") (class "Default")
      (node (ref "PAD36") (pin "1") (pinfunction "P_1") (pintype "passive"))
      (node (ref "R18") (pin "1") (pinfunction "1_1") (pintype "passive"))
    )
    (net (code "45") (name "Net-(PAD37-P)") (class "Default")
      (node (ref "PAD37") (pin "1") (pinfunction "P_1") (pintype "passive"))
      (node (ref "U3") (pin "6") (pinfunction "DRAIN2_6") (pintype "output"))
    )
    (net (code "46") (name "Net-(PAD38-P)") (class "Default")
      (node (ref "PAD38") (pin "1") (pinfunction "P_1") (pintype "passive"))
      (node (ref "R19") (pin "1") (pinfunction "1_1") (pintype "passive"))
    )
    (net (code "47") (name "Net-(PAD39-P)") (class "Default")
      (node (ref "PAD39") (pin "1") (pinfunction "P_1") (pintype "passive"))
      (node (ref "U3") (pin "7") (pinfunction "DRAIN3_7") (pintype "output"))
    )
    (net (code "48") (name "Net-(PAD40-P)") (class "Default")
      (node (ref "PAD40") (pin "1") (pinfunction "P_1") (pintype "passive"))
      (node (ref "R20") (pin "1") (pinfunction "1_1") (pintype "passive"))
    )
    (net (code "49") (name "Net-(PAD41-P)") (class "Default")
      (node (ref "PAD41") (pin "1") (pinfunction "P_1") (pintype "passive"))
      (node (ref "U3") (pin "14") (pinfunction "DRAIN4_14") (pintype "output"))
    )
    (net (code "50") (name "Net-(PAD42-P)") (class "Default")
      (node (ref "PAD42") (pin "1") (pinfunction "P_1") (pintype "passive"))
      (node (ref "R21") (pin "1") (pinfunction "1_1") (pintype "passive"))
    )
    (net (code "51") (name "Net-(PAD43-P)") (class "Default")
      (node (ref "PAD43") (pin "1") (pinfunction "P_1") (pintype "passive"))
      (node (ref "U3") (pin "15") (pinfunction "DRAIN5_15") (pintype "output"))
    )
    (net (code "52") (name "Net-(PAD44-P)") (class "Default")
      (node (ref "PAD44") (pin "1") (pinfunction "P_1") (pintype "passive"))
      (node (ref "R22") (pin "1") (pinfunction "1_1") (pintype "passive"))
    )
    (net (code "53") (name "Net-(PAD45-P)") (class "Default")
      (node (ref "PAD45") (pin "1") (pinfunction "P_1") (pintype "passive"))
      (node (ref "U3") (pin "16") (pinfunction "DRAIN6_16") (pintype "output"))
    )
    (net (code "54") (name "Net-(PAD46-P)") (class "Default")
      (node (ref "PAD46") (pin "1") (pinfunction "P_1") (pintype "passive"))
      (node (ref "R23") (pin "1") (pinfunction "1_1") (pintype "passive"))
    )
    (net (code "55") (name "Net-(PAD47-P)") (class "Default")
      (node (ref "PAD47") (pin "1") (pinfunction "P_1") (pintype "passive"))
      (node (ref "U3") (pin "17") (pinfunction "DRAIN7_17") (pintype "output"))
    )
    (net (code "56") (name "Net-(PAD48-P)") (class "Default")
      (node (ref "PAD48") (pin "1") (pinfunction "P_1") (pintype "passive"))
      (node (ref "R24") (pin "1") (pinfunction "1_1") (pintype "passive"))
    )
    (net (code "57") (name "Net-(PAD49-P)") (class "Default")
      (node (ref "PAD49") (pin "1") (pinfunction "P_1") (pintype "passive"))
      (node (ref "U4") (pin "4") (pinfunction "DRAIN0_4") (pintype "output"))
    )
    (net (code "58") (name "Net-(PAD50-P)") (class "Default")
      (node (ref "PAD50") (pin "1") (pinfunction "P_1") (pintype "passive"))
      (node (ref "R25") (pin "1") (pinfunction "1_1") (pintype "passive"))
    )
    (net (code "59") (name "Net-(PAD51-P)") (class "Default")
      (node (ref "PAD51") (pin "1") (pinfunction "P_1") (pintype "passive"))
      (node (ref "U4") (pin "5") (pinfunction "DRAIN1_5") (pintype "output"))
    )
    (net (code "60") (name "Net-(PAD52-P)") (class "Default")
      (node (ref "PAD52") (pin "1") (pinfunction "P_1") (pintype "passive"))
      (node (ref "R26") (pin "1") (pinfunction "1_1") (pintype "passive"))
    )
    (net (code "61") (name "Net-(PAD53-P)") (class "Default")
      (node (ref "PAD53") (pin "1") (pinfunction "P_1") (pintype "passive"))
      (node (ref "U4") (pin "6") (pinfunction "DRAIN2_6") (pintype "output"))
    )
    (net (code "62") (name "Net-(PAD54-P)") (class "Default")
      (node (ref "PAD54") (pin "1") (pinfunction "P_1") (pintype "passive"))
      (node (ref "R27") (pin "1") (pinfunction "1_1") (pintype "passive"))
    )
    (net (code "63") (name "Net-(PAD55-P)") (class "Default")
      (node (ref "PAD55") (pin "1") (pinfunction "P_1") (pintype "passive"))
      (node (ref "U4") (pin "7") (pinfunction "DRAIN3_7") (pintype "output"))
    )
    (net (code "64") (name "Net-(PAD56-P)") (class "Default")
      (node (ref "PAD56") (pin "1") (pinfunction "P_1") (pintype "passive"))
      (node (ref "R28") (pin "1") (pinfunction "1_1") (pintype "passive"))
    )
    (net (code "65") (name "Net-(PAD57-P)") (class "Default")
      (node (ref "PAD57") (pin "1") (pinfunction "P_1") (pintype "passive"))
      (node (ref "U4") (pin "14") (pinfunction "DRAIN4_14") (pintype "output"))
    )
    (net (code "66") (name "Net-(PAD58-P)") (class "Default")
      (node (ref "PAD58") (pin "1") (pinfunction "P_1") (pintype "passive"))
      (node (ref "R29") (pin "1") (pinfunction "1_1") (pintype "passive"))
    )
    (net (code "67") (name "Net-(PAD59-P)") (class "Default")
      (node (ref "PAD59") (pin "1") (pinfunction "P_1") (pintype "passive"))
      (node (ref "U4") (pin "15") (pinfunction "DRAIN5_15") (pintype "output"))
    )
    (net (code "68") (name "Net-(PAD60-P)") (class "Default")
      (node (ref "PAD60") (pin "1") (pinfunction "P_1") (pintype "passive"))
      (node (ref "R30") (pin "1") (pinfunction "1_1") (pintype "passive"))
    )
    (net (code "69") (name "Net-(PAD61-P)") (class "Default")
      (node (ref "PAD61") (pin "1") (pinfunction "P_1") (pintype "passive"))
      (node (ref "U4") (pin "16") (pinfunction "DRAIN6_16") (pintype "output"))
    )
    (net (code "70") (name "Net-(PAD62-P)") (class "Default")
      (node (ref "PAD62") (pin "1") (pinfunction "P_1") (pintype "passive"))
      (node (ref "R31") (pin "1") (pinfunction "1_1") (pintype "passive"))
    )
    (net (code "71") (name "Net-(PAD63-P)") (class "Default")
      (node (ref "PAD63") (pin "1") (pinfunction "P_1") (pintype "passive"))
      (node (ref "U4") (pin "17") (pinfunction "DRAIN7_17") (pintype "output"))
    )
    (net (code "72") (name "Net-(PAD64-P)") (class "Default")
      (node (ref "PAD64") (pin "1") (pinfunction "P_1") (pintype "passive"))
      (node (ref "R32") (pin "1") (pinfunction "1_1") (pintype "passive"))
    )
    (net (code "73") (name "Net-(PAD65-P)") (class "Default")
      (node (ref "PAD65") (pin "1") (pinfunction "P_1") (pintype "passive"))
      (node (ref "U5") (pin "4") (pinfunction "DRAIN0_4") (pintype "output"))
    )
    (net (code "74") (name "Net-(PAD66-P)") (class "Default")
      (node (ref "PAD66") (pin "1") (pinfunction "P_1") (pintype "passive"))
      (node (ref "R33") (pin "1") (pinfunction "1_1") (pintype "passive"))
    )
    (net (code "75") (name "Net-(PAD67-P)") (class "Default")
      (node (ref "PAD67") (pin "1") (pinfunction "P_1") (pintype "passive"))
      (node (ref "U5") (pin "5") (pinfunction "DRAIN1_5") (pintype "output"))
    )
    (net (code "76") (name "Net-(PAD68-P)") (class "Default")
      (node (ref "PAD68") (pin "1") (pinfunction "P_1") (pintype "passive"))
      (node (ref "R34") (pin "1") (pinfunction "1_1") (pintype "passive"))
    )
    (net (code "77") (name "Net-(PAD69-P)") (class "Default")
      (node (ref "PAD69") (pin "1") (pinfunction "P_1") (pintype "passive"))
      (node (ref "U5") (pin "6") (pinfunction "DRAIN2_6") (pintype "output"))
    )
    (net (code "78") (name "Net-(PAD70-P)") (class "Default")
      (node (ref "PAD70") (pin "1") (pinfunction "P_1") (pintype "passive"))
      (node (ref "R35") (pin "1") (pinfunction "1_1") (pintype "passive"))
    )
    (net (code "79") (name "Net-(PAD71-P)") (class "Default")
      (node (ref "PAD71") (pin "1") (pinfunction "P_1") (pintype "passive"))
      (node (ref "U5") (pin "7") (pinfunction "DRAIN3_7") (pintype "output"))
    )
    (net (code "80") (name "Net-(PAD72-P)") (class "Default")
      (node (ref "PAD72") (pin "1") (pinfunction "P_1") (pintype "passive"))
      (node (ref "R36") (pin "1") (pinfunction "1_1") (pintype "passive"))
    )
    (net (code "81") (name "Net-(PAD73-P)") (class "Default")
      (node (ref "PAD73") (pin "1") (pinfunction "P_1") (pintype "passive"))
      (node (ref "U5") (pin "14") (pinfunction "DRAIN4_14") (pintype "output"))
    )
    (net (code "82") (name "Net-(PAD74-P)") (class "Default")
      (node (ref "PAD74") (pin "1") (pinfunction "P_1") (pintype "passive"))
      (node (ref "R37") (pin "1") (pinfunction "1_1") (pintype "passive"))
    )
    (net (code "83") (name "Net-(PAD75-P)") (class "Default")
      (node (ref "PAD75") (pin "1") (pinfunction "P_1") (pintype "passive"))
      (node (ref "U5") (pin "15") (pinfunction "DRAIN5_15") (pintype "output"))
    )
    (net (code "84") (name "Net-(PAD76-P)") (class "Default")
      (node (ref "PAD76") (pin "1") (pinfunction "P_1") (pintype "passive"))
      (node (ref "R38") (pin "1") (pinfunction "1_1") (pintype "passive"))
    )
    (net (code "85") (name "Net-(PAD77-P)") (class "Default")
      (node (ref "PAD77") (pin "1") (pinfunction "P_1") (pintype "passive"))
      (node (ref "U5") (pin "16") (pinfunction "DRAIN6_16") (pintype "output"))
    )
    (net (code "86") (name "Net-(PAD78-P)") (class "Default")
      (node (ref "PAD78") (pin "1") (pinfunction "P_1") (pintype "passive"))
      (node (ref "R39") (pin "1") (pinfunction "1_1") (pintype "passive"))
    )
    (net (code "87") (name "Net-(PAD79-P)") (class "Default")
      (node (ref "PAD79") (pin "1") (pinfunction "P_1") (pintype "passive"))
      (node (ref "U5") (pin "17") (pinfunction "DRAIN7_17") (pintype "output"))
    )
    (net (code "88") (name "Net-(PAD80-P)") (class "Default")
      (node (ref "PAD80") (pin "1") (pinfunction "P_1") (pintype "passive"))
      (node (ref "R40") (pin "1") (pinfunction "1_1") (pintype "passive"))
    )
    (net (code "89") (name "Net-(PAD81-P)") (class "Default")
      (node (ref "PAD81") (pin "1") (pinfunction "P_1") (pintype "passive"))
      (node (ref "U6") (pin "4") (pinfunction "DRAIN0_4") (pintype "output"))
    )
    (net (code "90") (name "Net-(PAD82-P)") (class "Default")
      (node (ref "PAD82") (pin "1") (pinfunction "P_1") (pintype "passive"))
      (node (ref "R41") (pin "1") (pinfunction "1_1") (pintype "passive"))
    )
    (net (code "91") (name "Net-(PAD83-P)") (class "Default")
      (node (ref "PAD83") (pin "1") (pinfunction "P_1") (pintype "passive"))
      (node (ref "U6") (pin "5") (pinfunction "DRAIN1_5") (pintype "output"))
    )
    (net (code "92") (name "Net-(PAD84-P)") (class "Default")
      (node (ref "PAD84") (pin "1") (pinfunction "P_1") (pintype "passive"))
      (node (ref "R42") (pin "1") (pinfunction "1_1") (pintype "passive"))
    )
    (net (code "93") (name "Net-(PAD85-P)") (class "Default")
      (node (ref "PAD85") (pin "1") (pinfunction "P_1") (pintype "passive"))
      (node (ref "U6") (pin "6") (pinfunction "DRAIN2_6") (pintype "output"))
    )
    (net (code "94") (name "Net-(PAD86-P)") (class "Default")
      (node (ref "PAD86") (pin "1") (pinfunction "P_1") (pintype "passive"))
      (node (ref "R43") (pin "1") (pinfunction "1_1") (pintype "passive"))
    )
    (net (code "95") (name "Net-(PAD87-P)") (class "Default")
      (node (ref "PAD87") (pin "1") (pinfunction "P_1") (pintype "passive"))
      (node (ref "U6") (pin "7") (pinfunction "DRAIN3_7") (pintype "output"))
    )
    (net (code "96") (name "Net-(PAD88-P)") (class "Default")
      (node (ref "PAD88") (pin "1") (pinfunction "P_1") (pintype "passive"))
      (node (ref "R44") (pin "1") (pinfunction "1_1") (pintype "passive"))
    )
    (net (code "97") (name "Net-(PAD89-P)") (class "Default")
      (node (ref "PAD89") (pin "1") (pinfunction "P_1") (pintype "passive"))
      (node (ref "U6") (pin "14") (pinfunction "DRAIN4_14") (pintype "output"))
    )
    (net (code "98") (name "Net-(PAD90-P)") (class "Default")
      (node (ref "PAD90") (pin "1") (pinfunction "P_1") (pintype "passive"))
      (node (ref "R45") (pin "1") (pinfunction "1_1") (pintype "passive"))
    )
    (net (code "99") (name "Net-(PAD91-P)") (class "Default")
      (node (ref "PAD91") (pin "1") (pinfunction "P_1") (pintype "passive"))
      (node (ref "U6") (pin "15") (pinfunction "DRAIN5_15") (pintype "output"))
    )
    (net (code "100") (name "Net-(PAD92-P)") (class "Default")
      (node (ref "PAD92") (pin "1") (pinfunction "P_1") (pintype "passive"))
      (node (ref "R46") (pin "1") (pinfunction "1_1") (pintype "passive"))
    )
    (net (code "101") (name "Net-(PAD93-P)") (class "Default")
      (node (ref "PAD93") (pin "1") (pinfunction "P_1") (pintype "passive"))
      (node (ref "U6") (pin "16") (pinfunction "DRAIN6_16") (pintype "output"))
    )
    (net (code "102") (name "Net-(PAD94-P)") (class "Default")
      (node (ref "PAD94") (pin "1") (pinfunction "P_1") (pintype "passive"))
      (node (ref "R47") (pin "1") (pinfunction "1_1") (pintype "passive"))
    )
    (net (code "103") (name "Net-(PAD95-P)") (class "Default")
      (node (ref "PAD95") (pin "1") (pinfunction "P_1") (pintype "passive"))
      (node (ref "U6") (pin "17") (pinfunction "DRAIN7_17") (pintype "output"))
    )
    (net (code "104") (name "Net-(PAD96-P)") (class "Default")
      (node (ref "PAD96") (pin "1") (pinfunction "P_1") (pintype "passive"))
      (node (ref "R48") (pin "1") (pinfunction "1_1") (pintype "passive"))
    )
    (net (code "105") (name "Net-(PAD97-P)") (class "Default")
      (node (ref "PAD97") (pin "1") (pinfunction "P_1") (pintype "passive"))
      (node (ref "U7") (pin "4") (pinfunction "DRAIN0_4") (pintype "output"))
    )
    (net (code "106") (name "Net-(PAD98-P)") (class "Default")
      (node (ref "PAD98") (pin "1") (pinfunction "P_1") (pintype "passive"))
      (node (ref "R49") (pin "1") (pinfunction "1_1") (pintype "passive"))
    )
    (net (code "107") (name "Net-(PAD99-P)") (class "Default")
      (node (ref "PAD99") (pin "1") (pinfunction "P_1") (pintype "passive"))
      (node (ref "U7") (pin "5") (pinfunction "DRAIN1_5") (pintype "output"))
    )
    (net (code "108") (name "Net-(PAD100-P)") (class "Default")
      (node (ref "PAD100") (pin "1") (pinfunction "P_1") (pintype "passive"))
      (node (ref "R50") (pin "1") (pinfunction "1_1") (pintype "passive"))
    )
    (net (code "109") (name "Net-(PAD101-P)") (class "Default")
      (node (ref "PAD101") (pin "1") (pinfunction "P_1") (pintype "passive"))
      (node (ref "U7") (pin "6") (pinfunction "DRAIN2_6") (pintype "output"))
    )
    (net (code "110") (name "Net-(PAD102-P)") (class "Default")
      (node (ref "PAD102") (pin "1") (pinfunction "P_1") (pintype "passive"))
      (node (ref "R51") (pin "1") (pinfunction "1_1") (pintype "passive"))
    )
    (net (code "111") (name "Net-(PAD103-P)") (class "Default")
      (node (ref "PAD103") (pin "1") (pinfunction "P_1") (pintype "passive"))
      (node (ref "U7") (pin "7") (pinfunction "DRAIN3_7") (pintype "output"))
    )
    (net (code "112") (name "Net-(PAD104-P)") (class "Default")
      (node (ref "PAD104") (pin "1") (pinfunction "P_1") (pintype "passive"))
      (node (ref "R52") (pin "1") (pinfunction "1_1") (pintype "passive"))
    )
    (net (code "113") (name "Net-(PAD105-P)") (class "Default")
      (node (ref "PAD105") (pin "1") (pinfunction "P_1") (pintype "passive"))
      (node (ref "U7") (pin "14") (pinfunction "DRAIN4_14") (pintype "output"))
    )
    (net (code "114") (name "Net-(PAD106-P)") (class "Default")
      (node (ref "PAD106") (pin "1") (pinfunction "P_1") (pintype "passive"))
      (node (ref "R53") (pin "1") (pinfunction "1_1") (pintype "passive"))
    )
    (net (code "115") (name "Net-(PAD107-P)") (class "Default")
      (node (ref "PAD107") (pin "1") (pinfunction "P_1") (pintype "passive"))
      (node (ref "U7") (pin "15") (pinfunction "DRAIN5_15") (pintype "output"))
    )
    (net (code "116") (name "Net-(PAD108-P)") (class "Default")
      (node (ref "PAD108") (pin "1") (pinfunction "P_1") (pintype "passive"))
      (node (ref "R54") (pin "1") (pinfunction "1_1") (pintype "passive"))
    )
    (net (code "117") (name "Net-(PAD109-P)") (class "Default")
      (node (ref "PAD109") (pin "1") (pinfunction "P_1") (pintype "passive"))
      (node (ref "U7") (pin "16") (pinfunction "DRAIN6_16") (pintype "output"))
    )
    (net (code "118") (name "Net-(PAD110-P)") (class "Default")
      (node (ref "PAD110") (pin "1") (pinfunction "P_1") (pintype "passive"))
      (node (ref "R55") (pin "1") (pinfunction "1_1") (pintype "passive"))
    )
    (net (code "119") (name "Net-(PAD111-P)") (class "Default")
      (node (ref "PAD111") (pin "1") (pinfunction "P_1") (pintype "passive"))
      (node (ref "U7") (pin "17") (pinfunction "DRAIN7_17") (pintype "output"))
    )
    (net (code "120") (name "Net-(PAD112-P)") (class "Default")
      (node (ref "PAD112") (pin "1") (pinfunction "P_1") (pintype "passive"))
      (node (ref "R56") (pin "1") (pinfunction "1_1") (pintype "passive"))
    )
    (net (code "121") (name "Net-(PAD113-P)") (class "Default")
      (node (ref "PAD113") (pin "1") (pinfunction "P_1") (pintype "passive"))
      (node (ref "U8") (pin "4") (pinfunction "DRAIN0_4") (pintype "output"))
    )
    (net (code "122") (name "Net-(PAD114-P)") (class "Default")
      (node (ref "PAD114") (pin "1") (pinfunction "P_1") (pintype "passive"))
      (node (ref "R57") (pin "1") (pinfunction "1_1") (pintype "passive"))
    )
    (net (code "123") (name "Net-(PAD115-P)") (class "Default")
      (node (ref "PAD115") (pin "1") (pinfunction "P_1") (pintype "passive"))
      (node (ref "U8") (pin "5") (pinfunction "DRAIN1_5") (pintype "output"))
    )
    (net (code "124") (name "Net-(PAD116-P)") (class "Default")
      (node (ref "PAD116") (pin "1") (pinfunction "P_1") (pintype "passive"))
      (node (ref "R58") (pin "1") (pinfunction "1_1") (pintype "passive"))
    )
    (net (code "125") (name "Net-(PAD117-P)") (class "Default")
      (node (ref "PAD117") (pin "1") (pinfunction "P_1") (pintype "passive"))
      (node (ref "U8") (pin "6") (pinfunction "DRAIN2_6") (pintype "output"))
    )
    (net (code "126") (name "Net-(PAD118-P)") (class "Default")
      (node (ref "PAD118") (pin "1") (pinfunction "P_1") (pintype "passive"))
      (node (ref "R59") (pin "1") (pinfunction "1_1") (pintype "passive"))
    )
    (net (code "127") (name "Net-(PAD119-P)") (class "Default")
      (node (ref "PAD119") (pin "1") (pinfunction "P_1") (pintype "passive"))
      (node (ref "U8") (pin "7") (pinfunction "DRAIN3_7") (pintype "output"))
    )
    (net (code "128") (name "Net-(PAD120-P)") (class "Default")
      (node (ref "PAD120") (pin "1") (pinfunction "P_1") (pintype "passive"))
      (node (ref "R60") (pin "1") (pinfunction "1_1") (pintype "passive"))
    )
    (net (code "129") (name "Net-(PAD121-P)") (class "Default")
      (node (ref "PAD121") (pin "1") (pinfunction "P_1") (pintype "passive"))
      (node (ref "U8") (pin "14") (pinfunction "DRAIN4_14") (pintype "output"))
    )
    (net (code "130") (name "Net-(PAD122-P)") (class "Default")
      (node (ref "PAD122") (pin "1") (pinfunction "P_1") (pintype "passive"))
      (node (ref "R61") (pin "1") (pinfunction "1_1") (pintype "passive"))
    )
    (net (code "131") (name "Net-(PAD123-P)") (class "Default")
      (node (ref "PAD123") (pin "1") (pinfunction "P_1") (pintype "passive"))
      (node (ref "U8") (pin "15") (pinfunction "DRAIN5_15") (pintype "output"))
    )
    (net (code "132") (name "Net-(PAD124-P)") (class "Default")
      (node (ref "PAD124") (pin "1") (pinfunction "P_1") (pintype "passive"))
      (node (ref "R62") (pin "1") (pinfunction "1_1") (pintype "passive"))
    )
    (net (code "133") (name "Net-(PAD125-P)") (class "Default")
      (node (ref "PAD125") (pin "1") (pinfunction "P_1") (pintype "passive"))
      (node (ref "U8") (pin "16") (pinfunction "DRAIN6_16") (pintype "output"))
    )
    (net (code "134") (name "Net-(PAD126-P)") (class "Default")
      (node (ref "PAD126") (pin "1") (pinfunction "P_1") (pintype "passive"))
      (node (ref "R63") (pin "1") (pinfunction "1_1") (pintype "passive"))
    )
    (net (code "135") (name "Net-(PAD127-P)") (class "Default")
      (node (ref "PAD127") (pin "1") (pinfunction "P_1") (pintype "passive"))
      (node (ref "U8") (pin "17") (pinfunction "DRAIN7_17") (pintype "output"))
    )
    (net (code "136") (name "Net-(PAD128-P)") (class "Default")
      (node (ref "PAD128") (pin "1") (pinfunction "P_1") (pintype "passive"))
      (node (ref "R64") (pin "1") (pinfunction "1_1") (pintype "passive"))
    )
    (net (code "137") (name "Net-(PAD129-P)") (class "Default")
      (node (ref "PAD129") (pin "1") (pinfunction "P_1") (pintype "passive"))
      (node (ref "U10") (pin "4") (pinfunction "DRAIN0_4") (pintype "output"))
    )
    (net (code "138") (name "Net-(PAD130-P)") (class "Default")
      (node (ref "PAD130") (pin "1") (pinfunction "P_1") (pintype "passive"))
      (node (ref "R65") (pin "1") (pinfunction "1_1") (pintype "passive"))
    )
    (net (code "139") (name "Net-(PAD131-P)") (class "Default")
      (node (ref "PAD131") (pin "1") (pinfunction "P_1") (pintype "passive"))
      (node (ref "U10") (pin "5") (pinfunction "DRAIN1_5") (pintype "output"))
    )
    (net (code "140") (name "Net-(PAD132-P)") (class "Default")
      (node (ref "PAD132") (pin "1") (pinfunction "P_1") (pintype "passive"))
      (node (ref "R66") (pin "1") (pinfunction "1_1") (pintype "passive"))
    )
    (net (code "141") (name "Net-(PAD133-P)") (class "Default")
      (node (ref "PAD133") (pin "1") (pinfunction "P_1") (pintype "passive"))
      (node (ref "U10") (pin "6") (pinfunction "DRAIN2_6") (pintype "output"))
    )
    (net (code "142") (name "Net-(PAD134-P)") (class "Default")
      (node (ref "PAD134") (pin "1") (pinfunction "P_1") (pintype "passive"))
      (node (ref "R67") (pin "1") (pinfunction "1_1") (pintype "passive"))
    )
    (net (code "143") (name "Net-(PAD135-P)") (class "Default")
      (node (ref "PAD135") (pin "1") (pinfunction "P_1") (pintype "passive"))
      (node (ref "U10") (pin "7") (pinfunction "DRAIN3_7") (pintype "output"))
    )
    (net (code "144") (name "Net-(PAD136-P)") (class "Default")
      (node (ref "PAD136") (pin "1") (pinfunction "P_1") (pintype "passive"))
      (node (ref "R68") (pin "1") (pinfunction "1_1") (pintype "passive"))
    )
    (net (code "145") (name "Net-(PAD137-P)") (class "Default")
      (node (ref "PAD137") (pin "1") (pinfunction "P_1") (pintype "passive"))
      (node (ref "U10") (pin "14") (pinfunction "DRAIN4_14") (pintype "output"))
    )
    (net (code "146") (name "Net-(PAD138-P)") (class "Default")
      (node (ref "PAD138") (pin "1") (pinfunction "P_1") (pintype "passive"))
      (node (ref "R69") (pin "1") (pinfunction "1_1") (pintype "passive"))
    )
    (net (code "147") (name "Net-(U1-GND)") (class "Default")
      (node (ref "RG") (pin "2") (pinfunction "2_2") (pintype "passive"))
      (node (ref "U$59") (pin "GND") (pinfunction "GND_GND") (pintype "bidirectional"))
      (node (ref "U1") (pin "10") (pinfunction "GND_3_10") (pintype "passive"))
      (node (ref "U1") (pin "11") (pinfunction "GND_11") (pintype "passive"))
      (node (ref "U1") (pin "19") (pinfunction "GND_2_19") (pintype "passive"))
      (node (ref "U10") (pin "10") (pinfunction "GND_3_10") (pintype "passive"))
      (node (ref "U10") (pin "11") (pinfunction "GND_11") (pintype "passive"))
      (node (ref "U10") (pin "19") (pinfunction "GND_2_19") (pintype "passive"))
      (node (ref "U11") (pin "10") (pinfunction "GND_3_10") (pintype "passive"))
      (node (ref "U11") (pin "11") (pinfunction "GND_11") (pintype "passive"))
      (node (ref "U11") (pin "19") (pinfunction "GND_2_19") (pintype "passive"))
      (node (ref "U12") (pin "10") (pinfunction "GND_3_10") (pintype "passive"))
      (node (ref "U12") (pin "11") (pinfunction "GND_11") (pintype "passive"))
      (node (ref "U12") (pin "19") (pinfunction "GND_2_19") (pintype "passive"))
      (node (ref "U13") (pin "10") (pinfunction "GND_3_10") (pintype "passive"))
      (node (ref "U13") (pin "11") (pinfunction "GND_11") (pintype "passive"))
      (node (ref "U13") (pin "19") (pinfunction "GND_2_19") (pintype "passive"))
      (node (ref "U14") (pin "10") (pinfunction "GND_3_10") (pintype "passive"))
      (node (ref "U14") (pin "11") (pinfunction "GND_11") (pintype "passive"))
      (node (ref "U14") (pin "19") (pinfunction "GND_2_19") (pintype "passive"))
      (node (ref "U15") (pin "10") (pinfunction "GND_3_10") (pintype "passive"))
      (node (ref "U15") (pin "11") (pinfunction "GND_11") (pintype "passive"))
      (node (ref "U15") (pin "19") (pinfunction "GND_2_19") (pintype "passive"))
      (node (ref "U16") (pin "10") (pinfunction "GND_3_10") (pintype "passive"))
      (node (ref "U16") (pin "11") (pinfunction "GND_11") (pintype "passive"))
      (node (ref "U16") (pin "19") (pinfunction "GND_2_19") (pintype "passive"))
      (node (ref "U17") (pin "10") (pinfunction "GND_3_10") (pintype "passive"))
      (node (ref "U17") (pin "11") (pinfunction "GND_11") (pintype "passive"))
      (node (ref "U17") (pin "19") (pinfunction "GND_2_19") (pintype "passive"))
      (node (ref "U18") (pin "10") (pinfunction "GND_3_10") (pintype "passive"))
      (node (ref "U18") (pin "11") (pinfunction "GND_11") (pintype "passive"))
      (node (ref "U18") (pin "19") (pinfunction "GND_2_19") (pintype "passive"))
      (node (ref "U19") (pin "7") (pinfunction "GND_7") (pintype "bidirectional"))
      (node (ref "U2") (pin "10") (pinfunction "GND_3_10") (pintype "passive"))
      (node (ref "U2") (pin "11") (pinfunction "GND_11") (pintype "passive"))
      (node (ref "U2") (pin "19") (pinfunction "GND_2_19") (pintype "passive"))
      (node (ref "U3") (pin "10") (pinfunction "GND_3_10") (pintype "passive"))
      (node (ref "U3") (pin "11") (pinfunction "GND_11") (pintype "passive"))
      (node (ref "U3") (pin "19") (pinfunction "GND_2_19") (pintype "passive"))
      (node (ref "U4") (pin "10") (pinfunction "GND_3_10") (pintype "passive"))
      (node (ref "U4") (pin "11") (pinfunction "GND_11") (pintype "passive"))
      (node (ref "U4") (pin "19") (pinfunction "GND_2_19") (pintype "passive"))
      (node (ref "U5") (pin "10") (pinfunction "GND_3_10") (pintype "passive"))
      (node (ref "U5") (pin "11") (pinfunction "GND_11") (pintype "passive"))
      (node (ref "U5") (pin "19") (pinfunction "GND_2_19") (pintype "passive"))
      (node (ref "U6") (pin "10") (pinfunction "GND_3_10") (pintype "passive"))
      (node (ref "U6") (pin "11") (pinfunction "GND_11") (pintype "passive"))
      (node (ref "U6") (pin "19") (pinfunction "GND_2_19") (pintype "passive"))
      (node (ref "U7") (pin "10") (pinfunction "GND_3_10") (pintype "passive"))
      (node (ref "U7") (pin "11") (pinfunction "GND_11") (pintype "passive"))
      (node (ref "U7") (pin "19") (pinfunction "GND_2_19") (pintype "passive"))
      (node (ref "U8") (pin "10") (pinfunction "GND_3_10") (pintype "passive"))
      (node (ref "U8") (pin "11") (pinfunction "GND_11") (pintype "passive"))
      (node (ref "U8") (pin "19") (pinfunction "GND_2_19") (pintype "passive"))
      (node (ref "U9") (pin "10") (pinfunction "GND_3_10") (pintype "passive"))
      (node (ref "U9") (pin "11") (pinfunction "GND_11") (pintype "passive"))
      (node (ref "U9") (pin "19") (pinfunction "GND_2_19") (pintype "passive"))
    )
    (net (code "148") (name "Net-(U1-RCK)") (class "Default")
      (node (ref "U1") (pin "12") (pinfunction "RCK_12") (pintype "input"))
      (node (ref "U1") (pin "13") (pinfunction "SRCK_13") (pintype "input"))
      (node (ref "U10") (pin "12") (pinfunction "RCK_12") (pintype "input"))
      (node (ref "U10") (pin "13") (pinfunction "SRCK_13") (pintype "input"))
      (node (ref "U11") (pin "12") (pinfunction "RCK_12") (pintype "input"))
      (node (ref "U11") (pin "13") (pinfunction "SRCK_13") (pintype "input"))
      (node (ref "U12") (pin "12") (pinfunction "RCK_12") (pintype "input"))
      (node (ref "U12") (pin "13") (pinfunction "SRCK_13") (pintype "input"))
      (node (ref "U13") (pin "12") (pinfunction "RCK_12") (pintype "input"))
      (node (ref "U13") (pin "13") (pinfunction "SRCK_13") (pintype "input"))
      (node (ref "U14") (pin "12") (pinfunction "RCK_12") (pintype "input"))
      (node (ref "U14") (pin "13") (pinfunction "SRCK_13") (pintype "input"))
      (node (ref "U15") (pin "12") (pinfunction "RCK_12") (pintype "input"))
      (node (ref "U15") (pin "13") (pinfunction "SRCK_13") (pintype "input"))
      (node (ref "U16") (pin "12") (pinfunction "RCK_12") (pintype "input"))
      (node (ref "U16") (pin "13") (pinfunction "SRCK_13") (pintype "input"))
      (node (ref "U17") (pin "12") (pinfunction "RCK_12") (pintype "input"))
      (node (ref "U17") (pin "13") (pinfunction "SRCK_13") (pintype "input"))
      (node (ref "U18") (pin "12") (pinfunction "RCK_12") (pintype "input"))
      (node (ref "U18") (pin "13") (pinfunction "SRCK_13") (pintype "input"))
      (node (ref "U19") (pin "11") (pinfunction "B3_11") (pintype "bidirectional"))
      (node (ref "U2") (pin "12") (pinfunction "RCK_12") (pintype "input"))
      (node (ref "U2") (pin "13") (pinfunction "SRCK_13") (pintype "input"))
      (node (ref "U3") (pin "12") (pinfunction "RCK_12") (pintype "input"))
      (node (ref "U3") (pin "13") (pinfunction "SRCK_13") (pintype "input"))
      (node (ref "U4") (pin "12") (pinfunction "RCK_12") (pintype "input"))
      (node (ref "U4") (pin "13") (pinfunction "SRCK_13") (pintype "input"))
      (node (ref "U5") (pin "12") (pinfunction "RCK_12") (pintype "input"))
      (node (ref "U5") (pin "13") (pinfunction "SRCK_13") (pintype "input"))
      (node (ref "U6") (pin "12") (pinfunction "RCK_12") (pintype "input"))
      (node (ref "U6") (pin "13") (pinfunction "SRCK_13") (pintype "input"))
      (node (ref "U7") (pin "12") (pinfunction "RCK_12") (pintype "input"))
      (node (ref "U7") (pin "13") (pinfunction "SRCK_13") (pintype "input"))
      (node (ref "U8") (pin "12") (pinfunction "RCK_12") (pintype "input"))
      (node (ref "U8") (pin "13") (pinfunction "SRCK_13") (pintype "input"))
      (node (ref "U9") (pin "12") (pinfunction "RCK_12") (pintype "input"))
      (node (ref "U9") (pin "13") (pinfunction "SRCK_13") (pintype "input"))
    )
    (net (code "149") (name "Net-(U1-SER_IN)") (class "Default")
      (node (ref "U1") (pin "3") (pinfunction "SER_IN_3") (pintype "input"))
      (node (ref "U19") (pin "13") (pinfunction "B1_13") (pintype "bidirectional"))
    )
    (net (code "150") (name "Net-(U1-SER_OUT)") (class "Default")
      (node (ref "U1") (pin "18") (pinfunction "SER_OUT_18") (pintype "output"))
      (node (ref "U2") (pin "3") (pinfunction "SER_IN_3") (pintype "input"))
    )
    (net (code "151") (name "Net-(U1-VCC)") (class "Default")
      (node (ref "R5V") (pin "2") (pinfunction "2_2") (pintype "passive"))
      (node (ref "U$59") (pin "VIN") (pinfunction "VIN_VIN") (pintype "bidirectional"))
      (node (ref "U1") (pin "2") (pinfunction "VCC_2") (pintype "power_in"))
      (node (ref "U10") (pin "2") (pinfunction "VCC_2") (pintype "power_in"))
      (node (ref "U11") (pin "2") (pinfunction "VCC_2") (pintype "power_in"))
      (node (ref "U12") (pin "2") (pinfunction "VCC_2") (pintype "power_in"))
      (node (ref "U13") (pin "2") (pinfunction "VCC_2") (pintype "power_in"))
      (node (ref "U14") (pin "2") (pinfunction "VCC_2") (pintype "power_in"))
      (node (ref "U15") (pin "2") (pinfunction "VCC_2") (pintype "power_in"))
      (node (ref "U16") (pin "2") (pinfunction "VCC_2") (pintype "power_in"))
      (node (ref "U17") (pin "2") (pinfunction "VCC_2") (pintype "power_in"))
      (node (ref "U18") (pin "2") (pinfunction "VCC_2") (pintype "power_in"))
      (node (ref "U19") (pin "14") (pinfunction "VCCB_14") (pintype "bidirectional"))
      (node (ref "U2") (pin "2") (pinfunction "VCC_2") (pintype "power_in"))
      (node (ref "U3") (pin "2") (pinfunction "VCC_2") (pintype "power_in"))
      (node (ref "U4") (pin "2") (pinfunction "VCC_2") (pintype "power_in"))
      (node (ref "U5") (pin "2") (pinfunction "VCC_2") (pintype "power_in"))
      (node (ref "U6") (pin "2") (pinfunction "VCC_2") (pintype "power_in"))
      (node (ref "U7") (pin "2") (pinfunction "VCC_2") (pintype "power_in"))
      (node (ref "U8") (pin "2") (pinfunction "VCC_2") (pintype "power_in"))
      (node (ref "U9") (pin "2") (pinfunction "VCC_2") (pintype "power_in"))
    )
    (net (code "152") (name "Net-(U1-~{G})") (class "Default")
      (node (ref "U1") (pin "9") (pinfunction "~{G}_9") (pintype "input"))
      (node (ref "U10") (pin "9") (pinfunction "~{G}_9") (pintype "input"))
      (node (ref "U11") (pin "9") (pinfunction "~{G}_9") (pintype "input"))
      (node (ref "U12") (pin "9") (pinfunction "~{G}_9") (pintype "input"))
      (node (ref "U13") (pin "9") (pinfunction "~{G}_9") (pintype "input"))
      (node (ref "U14") (pin "9") (pinfunction "~{G}_9") (pintype "input"))
      (node (ref "U15") (pin "9") (pinfunction "~{G}_9") (pintype "input"))
      (node (ref "U16") (pin "9") (pinfunction "~{G}_9") (pintype "input"))
      (node (ref "U17") (pin "9") (pinfunction "~{G}_9") (pintype "input"))
      (node (ref "U18") (pin "9") (pinfunction "~{G}_9") (pintype "input"))
      (node (ref "U19") (pin "10") (pinfunction "B4_10") (pintype "bidirectional"))
      (node (ref "U2") (pin "9") (pinfunction "~{G}_9") (pintype "input"))
      (node (ref "U3") (pin "9") (pinfunction "~{G}_9") (pintype "input"))
      (node (ref "U4") (pin "9") (pinfunction "~{G}_9") (pintype "input"))
      (node (ref "U5") (pin "9") (pinfunction "~{G}_9") (pintype "input"))
      (node (ref "U6") (pin "9") (pinfunction "~{G}_9") (pintype "input"))
      (node (ref "U7") (pin "9") (pinfunction "~{G}_9") (pintype "input"))
      (node (ref "U8") (pin "9") (pinfunction "~{G}_9") (pintype "input"))
      (node (ref "U9") (pin "9") (pinfunction "~{G}_9") (pintype "input"))
    )
    (net (code "153") (name "Net-(U1-~{SRCLR})") (class "Default")
      (node (ref "R5V") (pin "1") (pinfunction "1_1") (pintype "passive"))
      (node (ref "RG") (pin "1") (pinfunction "1_1") (pintype "passive"))
      (node (ref "U1") (pin "8") (pinfunction "~{SRCLR}_8") (pintype "input"))
      (node (ref "U10") (pin "8") (pinfunction "~{SRCLR}_8") (pintype "input"))
      (node (ref "U11") (pin "8") (pinfunction "~{SRCLR}_8") (pintype "input"))
      (node (ref "U12") (pin "8") (pinfunction "~{SRCLR}_8") (pintype "input"))
      (node (ref "U13") (pin "8") (pinfunction "~{SRCLR}_8") (pintype "input"))
      (node (ref "U14") (pin "8") (pinfunction "~{SRCLR}_8") (pintype "input"))
      (node (ref "U15") (pin "8") (pinfunction "~{SRCLR}_8") (pintype "input"))
      (node (ref "U16") (pin "8") (pinfunction "~{SRCLR}_8") (pintype "input"))
      (node (ref "U17") (pin "8") (pinfunction "~{SRCLR}_8") (pintype "input"))
      (node (ref "U18") (pin "8") (pinfunction "~{SRCLR}_8") (pintype "input"))
      (node (ref "U2") (pin "8") (pinfunction "~{SRCLR}_8") (pintype "input"))
      (node (ref "U3") (pin "8") (pinfunction "~{SRCLR}_8") (pintype "input"))
      (node (ref "U4") (pin "8") (pinfunction "~{SRCLR}_8") (pintype "input"))
      (node (ref "U5") (pin "8") (pinfunction "~{SRCLR}_8") (pintype "input"))
      (node (ref "U6") (pin "8") (pinfunction "~{SRCLR}_8") (pintype "input"))
      (node (ref "U7") (pin "8") (pinfunction "~{SRCLR}_8") (pintype "input"))
      (node (ref "U8") (pin "8") (pinfunction "~{SRCLR}_8") (pintype "input"))
      (node (ref "U9") (pin "8") (pinfunction "~{SRCLR}_8") (pintype "input"))
    )
    (net (code "154") (name "Net-(U2-SER_OUT)") (class "Default")
      (node (ref "U2") (pin "18") (pinfunction "SER_OUT_18") (pintype "output"))
      (node (ref "U3") (pin "3") (pinfunction "SER_IN_3") (pintype "input"))
    )
    (net (code "155") (name "Net-(U3-SER_OUT)") (class "Default")
      (node (ref "U3") (pin "18") (pinfunction "SER_OUT_18") (pintype "output"))
      (node (ref "U4") (pin "3") (pinfunction "SER_IN_3") (pintype "input"))
    )
    (net (code "156") (name "Net-(U4-SER_OUT)") (class "Default")
      (node (ref "U4") (pin "18") (pinfunction "SER_OUT_18") (pintype "output"))
      (node (ref "U5") (pin "3") (pinfunction "SER_IN_3") (pintype "input"))
    )
    (net (code "157") (name "Net-(U5-SER_OUT)") (class "Default")
      (node (ref "U5") (pin "18") (pinfunction "SER_OUT_18") (pintype "output"))
      (node (ref "U6") (pin "3") (pinfunction "SER_IN_3") (pintype "input"))
    )
    (net (code "158") (name "Net-(U6-SER_OUT)") (class "Default")
      (node (ref "U6") (pin "18") (pinfunction "SER_OUT_18") (pintype "output"))
      (node (ref "U7") (pin "3") (pinfunction "SER_IN_3") (pintype "input"))
    )
    (net (code "159") (name "Net-(U7-SER_OUT)") (class "Default")
      (node (ref "U7") (pin "18") (pinfunction "SER_OUT_18") (pintype "output"))
      (node (ref "U8") (pin "3") (pinfunction "SER_IN_3") (pintype "input"))
    )
    (net (code "160") (name "Net-(U9-DRAIN0)") (class "Default")
      (node (ref "R1") (pin "2") (pinfunction "2_2") (pintype "passive"))
      (node (ref "U9") (pin "4") (pinfunction "DRAIN0_4") (pintype "output"))
    )
    (net (code "161") (name "Net-(U9-DRAIN1)") (class "Default")
      (node (ref "R2") (pin "2") (pinfunction "2_2") (pintype "passive"))
      (node (ref "U9") (pin "5") (pinfunction "DRAIN1_5") (pintype "output"))
    )
    (net (code "162") (name "Net-(U9-DRAIN2)") (class "Default")
      (node (ref "R3") (pin "2") (pinfunction "2_2") (pintype "passive"))
      (node (ref "U9") (pin "6") (pinfunction "DRAIN2_6") (pintype "output"))
    )
    (net (code "163") (name "Net-(U9-DRAIN3)") (class "Default")
      (node (ref "R4") (pin "2") (pinfunction "2_2") (pintype "passive"))
      (node (ref "U9") (pin "7") (pinfunction "DRAIN3_7") (pintype "output"))
    )
    (net (code "164") (name "Net-(U9-DRAIN4)") (class "Default")
      (node (ref "R5") (pin "2") (pinfunction "2_2") (pintype "passive"))
      (node (ref "U9") (pin "14") (pinfunction "DRAIN4_14") (pintype "output"))
    )
    (net (code "165") (name "Net-(U9-DRAIN5)") (class "Default")
      (node (ref "R6") (pin "2") (pinfunction "2_2") (pintype "passive"))
      (node (ref "U9") (pin "15") (pinfunction "DRAIN5_15") (pintype "output"))
    )
    (net (code "166") (name "Net-(U9-DRAIN6)") (class "Default")
      (node (ref "R7") (pin "2") (pinfunction "2_2") (pintype "passive"))
      (node (ref "U9") (pin "16") (pinfunction "DRAIN6_16") (pintype "output"))
    )
    (net (code "167") (name "Net-(U9-DRAIN7)") (class "Default")
      (node (ref "R8") (pin "2") (pinfunction "2_2") (pintype "passive"))
      (node (ref "U9") (pin "17") (pinfunction "DRAIN7_17") (pintype "output"))
    )
    (net (code "168") (name "Net-(U10-SER_IN)") (class "Default")
      (node (ref "U10") (pin "3") (pinfunction "SER_IN_3") (pintype "input"))
      (node (ref "U8") (pin "18") (pinfunction "SER_OUT_18") (pintype "output"))
    )
    (net (code "169") (name "Net-(U11-DRAIN0)") (class "Default")
      (node (ref "R9") (pin "2") (pinfunction "2_2") (pintype "passive"))
      (node (ref "U11") (pin "4") (pinfunction "DRAIN0_4") (pintype "output"))
    )
    (net (code "170") (name "Net-(U11-DRAIN1)") (class "Default")
      (node (ref "R10") (pin "2") (pinfunction "2_2") (pintype "passive"))
      (node (ref "U11") (pin "5") (pinfunction "DRAIN1_5") (pintype "output"))
    )
    (net (code "171") (name "Net-(U11-DRAIN2)") (class "Default")
      (node (ref "R11") (pin "2") (pinfunction "2_2") (pintype "passive"))
      (node (ref "U11") (pin "6") (pinfunction "DRAIN2_6") (pintype "output"))
    )
    (net (code "172") (name "Net-(U11-DRAIN3)") (class "Default")
      (node (ref "R12") (pin "2") (pinfunction "2_2") (pintype "passive"))
      (node (ref "U11") (pin "7") (pinfunction "DRAIN3_7") (pintype "output"))
    )
    (net (code "173") (name "Net-(U11-DRAIN4)") (class "Default")
      (node (ref "R13") (pin "2") (pinfunction "2_2") (pintype "passive"))
      (node (ref "U11") (pin "14") (pinfunction "DRAIN4_14") (pintype "output"))
    )
    (net (code "174") (name "Net-(U11-DRAIN5)") (class "Default")
      (node (ref "R14") (pin "2") (pinfunction "2_2") (pintype "passive"))
      (node (ref "U11") (pin "15") (pinfunction "DRAIN5_15") (pintype "output"))
    )
    (net (code "175") (name "Net-(U11-DRAIN6)") (class "Default")
      (node (ref "R15") (pin "2") (pinfunction "2_2") (pintype "passive"))
      (node (ref "U11") (pin "16") (pinfunction "DRAIN6_16") (pintype "output"))
    )
    (net (code "176") (name "Net-(U11-DRAIN7)") (class "Default")
      (node (ref "R16") (pin "2") (pinfunction "2_2") (pintype "passive"))
      (node (ref "U11") (pin "17") (pinfunction "DRAIN7_17") (pintype "output"))
    )
    (net (code "177") (name "Net-(U11-SER_IN)") (class "Default")
      (node (ref "U11") (pin "3") (pinfunction "SER_IN_3") (pintype "input"))
      (node (ref "U9") (pin "18") (pinfunction "SER_OUT_18") (pintype "output"))
    )
    (net (code "178") (name "Net-(U11-SER_OUT)") (class "Default")
      (node (ref "U11") (pin "18") (pinfunction "SER_OUT_18") (pintype "output"))
      (node (ref "U12") (pin "3") (pinfunction "SER_IN_3") (pintype "input"))
    )
    (net (code "179") (name "Net-(U12-DRAIN0)") (class "Default")
      (node (ref "R17") (pin "2") (pinfunction "2_2") (pintype "passive"))
      (node (ref "U12") (pin "4") (pinfunction "DRAIN0_4") (pintype "output"))
    )
    (net (code "180") (name "Net-(U12-DRAIN1)") (class "Default")
      (node (ref "R18") (pin "2") (pinfunction "2_2") (pintype "passive"))
      (node (ref "U12") (pin "5") (pinfunction "DRAIN1_5") (pintype "output"))
    )
    (net (code "181") (name "Net-(U12-DRAIN2)") (class "Default")
      (node (ref "R19") (pin "2") (pinfunction "2_2") (pintype "passive"))
      (node (ref "U12") (pin "6") (pinfunction "DRAIN2_6") (pintype "output"))
    )
    (net (code "182") (name "Net-(U12-DRAIN3)") (class "Default")
      (node (ref "R20") (pin "2") (pinfunction "2_2") (pintype "passive"))
      (node (ref "U12") (pin "7") (pinfunction "DRAIN3_7") (pintype "output"))
    )
    (net (code "183") (name "Net-(U12-DRAIN4)") (class "Default")
      (node (ref "R21") (pin "2") (pinfunction "2_2") (pintype "passive"))
      (node (ref "U12") (pin "14") (pinfunction "DRAIN4_14") (pintype "output"))
    )
    (net (code "184") (name "Net-(U12-DRAIN5)") (class "Default")
      (node (ref "R22") (pin "2") (pinfunction "2_2") (pintype "passive"))
      (node (ref "U12") (pin "15") (pinfunction "DRAIN5_15") (pintype "output"))
    )
    (net (code "185") (name "Net-(U12-DRAIN6)") (class "Default")
      (node (ref "R23") (pin "2") (pinfunction "2_2") (pintype "passive"))
      (node (ref "U12") (pin "16") (pinfunction "DRAIN6_16") (pintype "output"))
    )
    (net (code "186") (name "Net-(U12-DRAIN7)") (class "Default")
      (node (ref "R24") (pin "2") (pinfunction "2_2") (pintype "passive"))
      (node (ref "U12") (pin "17") (pinfunction "DRAIN7_17") (pintype "output"))
    )
    (net (code "187") (name "Net-(U12-SER_OUT)") (class "Default")
      (node (ref "U12") (pin "18") (pinfunction "SER_OUT_18") (pintype "output"))
      (node (ref "U13") (pin "3") (pinfunction "SER_IN_3") (pintype "input"))
    )
    (net (code "188") (name "Net-(U13-DRAIN0)") (class "Default")
      (node (ref "R25") (pin "2") (pinfunction "2_2") (pintype "passive"))
      (node (ref "U13") (pin "4") (pinfunction "DRAIN0_4") (pintype "output"))
    )
    (net (code "189") (name "Net-(U13-DRAIN1)") (class "Default")
      (node (ref "R26") (pin "2") (pinfunction "2_2") (pintype "passive"))
      (node (ref "U13") (pin "5") (pinfunction "DRAIN1_5") (pintype "output"))
    )
    (net (code "190") (name "Net-(U13-DRAIN2)") (class "Default")
      (node (ref "R27") (pin "2") (pinfunction "2_2") (pintype "passive"))
      (node (ref "U13") (pin "6") (pinfunction "DRAIN2_6") (pintype "output"))
    )
    (net (code "191") (name "Net-(U13-DRAIN3)") (class "Default")
      (node (ref "R28") (pin "2") (pinfunction "2_2") (pintype "passive"))
      (node (ref "U13") (pin "7") (pinfunction "DRAIN3_7") (pintype "output"))
    )
    (net (code "192") (name "Net-(U13-DRAIN4)") (class "Default")
      (node (ref "R29") (pin "2") (pinfunction "2_2") (pintype "passive"))
      (node (ref "U13") (pin "14") (pinfunction "DRAIN4_14") (pintype "output"))
    )
    (net (code "193") (name "Net-(U13-DRAIN5)") (class "Default")
      (node (ref "R30") (pin "2") (pinfunction "2_2") (pintype "passive"))
      (node (ref "U13") (pin "15") (pinfunction "DRAIN5_15") (pintype "output"))
    )
    (net (code "194") (name "Net-(U13-DRAIN6)") (class "Default")
      (node (ref "R31") (pin "2") (pinfunction "2_2") (pintype "passive"))
      (node (ref "U13") (pin "16") (pinfunction "DRAIN6_16") (pintype "output"))
    )
    (net (code "195") (name "Net-(U13-DRAIN7)") (class "Default")
      (node (ref "R32") (pin "2") (pinfunction "2_2") (pintype "passive"))
      (node (ref "U13") (pin "17") (pinfunction "DRAIN7_17") (pintype "output"))
    )
    (net (code "196") (name "Net-(U13-SER_OUT)") (class "Default")
      (node (ref "U13") (pin "18") (pinfunction "SER_OUT_18") (pintype "output"))
      (node (ref "U14") (pin "3") (pinfunction "SER_IN_3") (pintype "input"))
    )
    (net (code "197") (name "Net-(U14-DRAIN0)") (class "Default")
      (node (ref "R33") (pin "2") (pinfunction "2_2") (pintype "passive"))
      (node (ref "U14") (pin "4") (pinfunction "DRAIN0_4") (pintype "output"))
    )
    (net (code "198") (name "Net-(U14-DRAIN1)") (class "Default")
      (node (ref "R34") (pin "2") (pinfunction "2_2") (pintype "passive"))
      (node (ref "U14") (pin "5") (pinfunction "DRAIN1_5") (pintype "output"))
    )
    (net (code "199") (name "Net-(U14-DRAIN2)") (class "Default")
      (node (ref "R35") (pin "2") (pinfunction "2_2") (pintype "passive"))
      (node (ref "U14") (pin "6") (pinfunction "DRAIN2_6") (pintype "output"))
    )
    (net (code "200") (name "Net-(U14-DRAIN3)") (class "Default")
      (node (ref "R36") (pin "2") (pinfunction "2_2") (pintype "passive"))
      (node (ref "U14") (pin "7") (pinfunction "DRAIN3_7") (pintype "output"))
    )
    (net (code "201") (name "Net-(U14-DRAIN4)") (class "Default")
      (node (ref "R37") (pin "2") (pinfunction "2_2") (pintype "passive"))
      (node (ref "U14") (pin "14") (pinfunction "DRAIN4_14") (pintype "output"))
    )
    (net (code "202") (name "Net-(U14-DRAIN5)") (class "Default")
      (node (ref "R38") (pin "2") (pinfunction "2_2") (pintype "passive"))
      (node (ref "U14") (pin "15") (pinfunction "DRAIN5_15") (pintype "output"))
    )
    (net (code "203") (name "Net-(U14-DRAIN6)") (class "Default")
      (node (ref "R39") (pin "2") (pinfunction "2_2") (pintype "passive"))
      (node (ref "U14") (pin "16") (pinfunction "DRAIN6_16") (pintype "output"))
    )
    (net (code "204") (name "Net-(U14-DRAIN7)") (class "Default")
      (node (ref "R40") (pin "2") (pinfunction "2_2") (pintype "passive"))
      (node (ref "U14") (pin "17") (pinfunction "DRAIN7_17") (pintype "output"))
    )
    (net (code "205") (name "Net-(U14-SER_OUT)") (class "Default")
      (node (ref "U14") (pin "18") (pinfunction "SER_OUT_18") (pintype "output"))
      (node (ref "U15") (pin "3") (pinfunction "SER_IN_3") (pintype "input"))
    )
    (net (code "206") (name "Net-(U15-DRAIN0)") (class "Default")
      (node (ref "R41") (pin "2") (pinfunction "2_2") (pintype "passive"))
      (node (ref "U15") (pin "4") (pinfunction "DRAIN0_4") (pintype "output"))
    )
    (net (code "207") (name "Net-(U15-DRAIN1)") (class "Default")
      (node (ref "R42") (pin "2") (pinfunction "2_2") (pintype "passive"))
      (node (ref "U15") (pin "5") (pinfunction "DRAIN1_5") (pintype "output"))
    )
    (net (code "208") (name "Net-(U15-DRAIN2)") (class "Default")
      (node (ref "R43") (pin "2") (pinfunction "2_2") (pintype "passive"))
      (node (ref "U15") (pin "6") (pinfunction "DRAIN2_6") (pintype "output"))
    )
    (net (code "209") (name "Net-(U15-DRAIN3)") (class "Default")
      (node (ref "R44") (pin "2") (pinfunction "2_2") (pintype "passive"))
      (node (ref "U15") (pin "7") (pinfunction "DRAIN3_7") (pintype "output"))
    )
    (net (code "210") (name "Net-(U15-DRAIN4)") (class "Default")
      (node (ref "R45") (pin "2") (pinfunction "2_2") (pintype "passive"))
      (node (ref "U15") (pin "14") (pinfunction "DRAIN4_14") (pintype "output"))
    )
    (net (code "211") (name "Net-(U15-DRAIN5)") (class "Default")
      (node (ref "R46") (pin "2") (pinfunction "2_2") (pintype "passive"))
      (node (ref "U15") (pin "15") (pinfunction "DRAIN5_15") (pintype "output"))
    )
    (net (code "212") (name "Net-(U15-DRAIN6)") (class "Default")
      (node (ref "R47") (pin "2") (pinfunction "2_2") (pintype "passive"))
      (node (ref "U15") (pin "16") (pinfunction "DRAIN6_16") (pintype "output"))
    )
    (net (code "213") (name "Net-(U15-DRAIN7)") (class "Default")
      (node (ref "R48") (pin "2") (pinfunction "2_2") (pintype "passive"))
      (node (ref "U15") (pin "17") (pinfunction "DRAIN7_17") (pintype "output"))
    )
    (net (code "214") (name "Net-(U15-SER_OUT)") (class "Default")
      (node (ref "U15") (pin "18") (pinfunction "SER_OUT_18") (pintype "output"))
      (node (ref "U16") (pin "3") (pinfunction "SER_IN_3") (pintype "input"))
    )
    (net (code "215") (name "Net-(U16-DRAIN0)") (class "Default")
      (node (ref "R49") (pin "2") (pinfunction "2_2") (pintype "passive"))
      (node (ref "U16") (pin "4") (pinfunction "DRAIN0_4") (pintype "output"))
    )
    (net (code "216") (name "Net-(U16-DRAIN1)") (class "Default")
      (node (ref "R50") (pin "2") (pinfunction "2_2") (pintype "passive"))
      (node (ref "U16") (pin "5") (pinfunction "DRAIN1_5") (pintype "output"))
    )
    (net (code "217") (name "Net-(U16-DRAIN2)") (class "Default")
      (node (ref "R51") (pin "2") (pinfunction "2_2") (pintype "passive"))
      (node (ref "U16") (pin "6") (pinfunction "DRAIN2_6") (pintype "output"))
    )
    (net (code "218") (name "Net-(U16-DRAIN3)") (class "Default")
      (node (ref "R52") (pin "2") (pinfunction "2_2") (pintype "passive"))
      (node (ref "U16") (pin "7") (pinfunction "DRAIN3_7") (pintype "output"))
    )
    (net (code "219") (name "Net-(U16-DRAIN4)") (class "Default")
      (node (ref "R53") (pin "2") (pinfunction "2_2") (pintype "passive"))
      (node (ref "U16") (pin "14") (pinfunction "DRAIN4_14") (pintype "output"))
    )
    (net (code "220") (name "Net-(U16-DRAIN5)") (class "Default")
      (node (ref "R54") (pin "2") (pinfunction "2_2") (pintype "passive"))
      (node (ref "U16") (pin "15") (pinfunction "DRAIN5_15") (pintype "output"))
    )
    (net (code "221") (name "Net-(U16-DRAIN6)") (class "Default")
      (node (ref "R55") (pin "2") (pinfunction "2_2") (pintype "passive"))
      (node (ref "U16") (pin "16") (pinfunction "DRAIN6_16") (pintype "output"))
    )
    (net (code "222") (name "Net-(U16-DRAIN7)") (class "Default")
      (node (ref "R56") (pin "2") (pinfunction "2_2") (pintype "passive"))
      (node (ref "U16") (pin "17") (pinfunction "DRAIN7_17") (pintype "output"))
    )
    (net (code "223") (name "Net-(U16-SER_OUT)") (class "Default")
      (node (ref "U16") (pin "18") (pinfunction "SER_OUT_18") (pintype "output"))
      (node (ref "U17") (pin "3") (pinfunction "SER_IN_3") (pintype "input"))
    )
    (net (code "224") (name "Net-(U17-DRAIN0)") (class "Default")
      (node (ref "R57") (pin "2") (pinfunction "2_2") (pintype "passive"))
      (node (ref "U17") (pin "4") (pinfunction "DRAIN0_4") (pintype "output"))
    )
    (net (code "225") (name "Net-(U17-DRAIN1)") (class "Default")
      (node (ref "R58") (pin "2") (pinfunction "2_2") (pintype "passive"))
      (node (ref "U17") (pin "5") (pinfunction "DRAIN1_5") (pintype "output"))
    )
    (net (code "226") (name "Net-(U17-DRAIN2)") (class "Default")
      (node (ref "R59") (pin "2") (pinfunction "2_2") (pintype "passive"))
      (node (ref "U17") (pin "6") (pinfunction "DRAIN2_6") (pintype "output"))
    )
    (net (code "227") (name "Net-(U17-DRAIN3)") (class "Default")
      (node (ref "R60") (pin "2") (pinfunction "2_2") (pintype "passive"))
      (node (ref "U17") (pin "7") (pinfunction "DRAIN3_7") (pintype "output"))
    )
    (net (code "228") (name "Net-(U17-DRAIN4)") (class "Default")
      (node (ref "R61") (pin "2") (pinfunction "2_2") (pintype "passive"))
      (node (ref "U17") (pin "14") (pinfunction "DRAIN4_14") (pintype "output"))
    )
    (net (code "229") (name "Net-(U17-DRAIN5)") (class "Default")
      (node (ref "R62") (pin "2") (pinfunction "2_2") (pintype "passive"))
      (node (ref "U17") (pin "15") (pinfunction "DRAIN5_15") (pintype "output"))
    )
    (net (code "230") (name "Net-(U17-DRAIN6)") (class "Default")
      (node (ref "R63") (pin "2") (pinfunction "2_2") (pintype "passive"))
      (node (ref "U17") (pin "16") (pinfunction "DRAIN6_16") (pintype "output"))
    )
    (net (code "231") (name "Net-(U17-DRAIN7)") (class "Default")
      (node (ref "R64") (pin "2") (pinfunction "2_2") (pintype "passive"))
      (node (ref "U17") (pin "17") (pinfunction "DRAIN7_17") (pintype "output"))
    )
    (net (code "232") (name "Net-(U17-SER_OUT)") (class "Default")
      (node (ref "U17") (pin "18") (pinfunction "SER_OUT_18") (pintype "output"))
      (node (ref "U18") (pin "3") (pinfunction "SER_IN_3") (pintype "input"))
    )
    (net (code "233") (name "Net-(U18-DRAIN0)") (class "Default")
      (node (ref "R65") (pin "2") (pinfunction "2_2") (pintype "passive"))
      (node (ref "U18") (pin "4") (pinfunction "DRAIN0_4") (pintype "output"))
    )
    (net (code "234") (name "Net-(U18-DRAIN1)") (class "Default")
      (node (ref "R66") (pin "2") (pinfunction "2_2") (pintype "passive"))
      (node (ref "U18") (pin "5") (pinfunction "DRAIN1_5") (pintype "output"))
    )
    (net (code "235") (name "Net-(U18-DRAIN2)") (class "Default")
      (node (ref "R67") (pin "2") (pinfunction "2_2") (pintype "passive"))
      (node (ref "U18") (pin "6") (pinfunction "DRAIN2_6") (pintype "output"))
    )
    (net (code "236") (name "Net-(U18-DRAIN3)") (class "Default")
      (node (ref "R68") (pin "2") (pinfunction "2_2") (pintype "passive"))
      (node (ref "U18") (pin "7") (pinfunction "DRAIN3_7") (pintype "output"))
    )
    (net (code "237") (name "Net-(U18-DRAIN4)") (class "Default")
      (node (ref "R69") (pin "2") (pinfunction "2_2") (pintype "passive"))
      (node (ref "U18") (pin "14") (pinfunction "DRAIN4_14") (pintype "output"))
    )
    (net (code "238") (name "Net-(U19-A1)") (class "Default")
      (node (ref "U$59") (pin "3/CANTX") (pinfunction "3/CANTX_3/CANTX") (pintype "bidirectional"))
      (node (ref "U19") (pin "2") (pinfunction "A1_2") (pintype "bidirectional"))
    )
    (net (code "239") (name "Net-(U19-A2)") (class "Default")
      (node (ref "U$59") (pin "4/CANRX") (pinfunction "4/CANRX_4/CANRX") (pintype "bidirectional"))
      (node (ref "U19") (pin "3") (pinfunction "A2_3") (pintype "bidirectional"))
    )
    (net (code "240") (name "Net-(U19-A3)") (class "Default")
      (node (ref "U$59") (pin "2") (pinfunction "2_2") (pintype "bidirectional"))
      (node (ref "U19") (pin "4") (pinfunction "A3_4") (pintype "bidirectional"))
    )
    (net (code "241") (name "Net-(U19-A4)") (class "Default")
      (node (ref "U$59") (pin "5") (pinfunction "5_5") (pintype "bidirectional"))
      (node (ref "U19") (pin "5") (pinfunction "A4_5") (pintype "bidirectional"))
    )
    (net (code "242") (name "Net-(U19-B2)") (class "Default")
      (node (ref "U19") (pin "12") (pinfunction "B2_12") (pintype "bidirectional"))
      (node (ref "U9") (pin "3") (pinfunction "SER_IN_3") (pintype "input"))
    )
    (net (code "243") (name "Net-(U19-OE)") (class "Default")
      (node (ref "U$59") (pin "7") (pinfunction "7_7") (pintype "bidirectional"))
      (node (ref "U19") (pin "8") (pinfunction "OE_8") (pintype "bidirectional"))
    )
    (net (code "244") (name "Net-(U19-VCCA)") (class "Default")
      (node (ref "U$59") (pin "3V3_LO") (pinfunction "3V3_LO_3V3_LO") (pintype "bidirectional"))
      (node (ref "U19") (pin "1") (pinfunction "VCCA_1") (pintype "bidirectional"))
    )
    (net (code "245") (name "unconnected-(J1-Pad9)") (class "Default")
      (node (ref "J1") (pin "9") (pinfunction "9_9") (pintype "passive"))
    )
    (net (code "246") (name "unconnected-(J1-Pad10)") (class "Default")
      (node (ref "J1") (pin "10") (pinfunction "10_10") (pintype "passive"))
    )
    (net (code "247") (name "unconnected-(U$59-A21{slash}DAC0-Pad21{slash}DAC0)") (class "Default")
      (node (ref "U$59") (pin "21/DAC0") (pinfunction "A21/DAC0_21/DAC0") (pintype "bidirectional"))
    )
    (net (code "248") (name "unconnected-(U$59-Pad1{slash}TX)") (class "Default")
      (node (ref "U$59") (pin "1/TX") (pinfunction "1/TX_1/TX") (pintype "bidirectional"))
    )
    (net (code "249") (name "unconnected-(U$59-Pad3V3)") (class "Default")
      (node (ref "U$59") (pin "3V3") (pinfunction "3V3_3V3") (pintype "bidirectional"))
    )
    (net (code "250") (name "unconnected-(U$59-Pad3V3_2)") (class "Default")
      (node (ref "U$59") (pin "3V3_2") (pinfunction "3V3_2_3V3_2") (pintype "bidirectional"))
    )
    (net (code "251") (name "unconnected-(U$59-Pad6)") (class "Default")
      (node (ref "U$59") (pin "6") (pinfunction "6_6") (pintype "bidirectional"))
    )
    (net (code "252") (name "unconnected-(U$59-Pad8)") (class "Default")
      (node (ref "U$59") (pin "8") (pinfunction "8_8") (pintype "bidirectional"))
    )
    (net (code "253") (name "unconnected-(U$59-Pad9{slash}CS)") (class "Default")
      (node (ref "U$59") (pin "9/CS") (pinfunction "9/CS_9/CS") (pintype "bidirectional"))
    )
    (net (code "254") (name "unconnected-(U$59-Pad10{slash}CS)") (class "Default")
      (node (ref "U$59") (pin "10/CS") (pinfunction "10/CS_10/CS") (pintype "bidirectional"))
    )
    (net (code "255") (name "unconnected-(U$59-Pad11{slash}MOSI)") (class "Default")
      (node (ref "U$59") (pin "11/MOSI") (pinfunction "11/MOSI_11/MOSI") (pintype "bidirectional"))
    )
    (net (code "256") (name "unconnected-(U$59-Pad12{slash}MISO)") (class "Default")
      (node (ref "U$59") (pin "12/MISO") (pinfunction "12/MISO_12/MISO") (pintype "bidirectional"))
    )
    (net (code "257") (name "unconnected-(U$59-Pad13{slash}SCK)") (class "Default")
      (node (ref "U$59") (pin "13/SCK") (pinfunction "13/SCK_13/SCK") (pintype "bidirectional"))
    )
    (net (code "258") (name "unconnected-(U$59-Pad14{slash}A0)") (class "Default")
      (node (ref "U$59") (pin "14/A0") (pinfunction "14/A0_14/A0") (pintype "bidirectional"))
    )
    (net (code "259") (name "unconnected-(U$59-Pad20{slash}A6)") (class "Default")
      (node (ref "U$59") (pin "20/A6") (pinfunction "20/A6_20/A6") (pintype "bidirectional"))
    )
    (net (code "260") (name "unconnected-(U$59-Pad21{slash}A7)") (class "Default")
      (node (ref "U$59") (pin "21/A7") (pinfunction "21/A7_21/A7") (pintype "bidirectional"))
    )
    (net (code "261") (name "unconnected-(U$59-Pad24)") (class "Default")
      (node (ref "U$59") (pin "24") (pinfunction "24_24") (pintype "bidirectional"))
    )
    (net (code "262") (name "unconnected-(U$59-Pad25)") (class "Default")
      (node (ref "U$59") (pin "25") (pinfunction "25_25") (pintype "bidirectional"))
    )
    (net (code "263") (name "unconnected-(U$59-Pad26)") (class "Default")
      (node (ref "U$59") (pin "26") (pinfunction "26_26") (pintype "bidirectional"))
    )
    (net (code "264") (name "unconnected-(U$59-Pad27)") (class "Default")
      (node (ref "U$59") (pin "27") (pinfunction "27_27") (pintype "bidirectional"))
    )
    (net (code "265") (name "unconnected-(U$59-Pad28)") (class "Default")
      (node (ref "U$59") (pin "28") (pinfunction "28_28") (pintype "bidirectional"))
    )
    (net (code "266") (name "unconnected-(U$59-Pad29)") (class "Default")
      (node (ref "U$59") (pin "29") (pinfunction "29_29") (pintype "bidirectional"))
    )
    (net (code "267") (name "unconnected-(U$59-Pad30)") (class "Default")
      (node (ref "U$59") (pin "30") (pinfunction "30_30") (pintype "bidirectional"))
    )
    (net (code "268") (name "unconnected-(U$59-Pad31{slash}A12)") (class "Default")
      (node (ref "U$59") (pin "31/A12") (pinfunction "31/A12_31/A12") (pintype "bidirectional"))
    )
    (net (code "269") (name "unconnected-(U$59-Pad32{slash}A13)") (class "Default")
      (node (ref "U$59") (pin "32/A13") (pinfunction "32/A13_32/A13") (pintype "bidirectional"))
    )
    (net (code "270") (name "unconnected-(U$59-Pad33{slash}A14)") (class "Default")
      (node (ref "U$59") (pin "33/A14") (pinfunction "33/A14_33/A14") (pintype "bidirectional"))
    )
    (net (code "271") (name "unconnected-(U$59-Pad34{slash}A15)") (class "Default")
      (node (ref "U$59") (pin "34/A15") (pinfunction "34/A15_34/A15") (pintype "bidirectional"))
    )
    (net (code "272") (name "unconnected-(U$59-Pad35{slash}A16)") (class "Default")
      (node (ref "U$59") (pin "35/A16") (pinfunction "35/A16_35/A16") (pintype "bidirectional"))
    )
    (net (code "273") (name "unconnected-(U$59-Pad36{slash}A17)") (class "Default")
      (node (ref "U$59") (pin "36/A17") (pinfunction "36/A17_36/A17") (pintype "bidirectional"))
    )
    (net (code "274") (name "unconnected-(U$59-Pad37{slash}A18)") (class "Default")
      (node (ref "U$59") (pin "37/A18") (pinfunction "37/A18_37/A18") (pintype "bidirectional"))
    )
    (net (code "275") (name "unconnected-(U$59-Pad38{slash}A19)") (class "Default")
      (node (ref "U$59") (pin "38/A19") (pinfunction "38/A19_38/A19") (pintype "bidirectional"))
    )
    (net (code "276") (name "unconnected-(U$59-Pad39{slash}A20)") (class "Default")
      (node (ref "U$59") (pin "39/A20") (pinfunction "39/A20_39/A20") (pintype "bidirectional"))
    )
    (net (code "277") (name "unconnected-(U$59-PadA10)") (class "Default")
      (node (ref "U$59") (pin "A10") (pinfunction "A10_A10") (pintype "bidirectional"))
    )
    (net (code "278") (name "unconnected-(U$59-PadA11)") (class "Default")
      (node (ref "U$59") (pin "A11") (pinfunction "A11_A11") (pintype "bidirectional"))
    )
    (net (code "279") (name "unconnected-(U$59-PadA22{slash}DAC1)") (class "Default")
      (node (ref "U$59") (pin "A22/DAC1") (pinfunction "A22/DAC1_A22/DAC1") (pintype "bidirectional"))
    )
    (net (code "280") (name "unconnected-(U$59-PadAGND)") (class "Default")
      (node (ref "U$59") (pin "AGND") (pinfunction "AGND_AGND") (pintype "bidirectional"))
    )
    (net (code "281") (name "unconnected-(U$59-PadAREF)") (class "Default")
      (node (ref "U$59") (pin "AREF") (pinfunction "AREF_AREF") (pintype "bidirectional"))
    )
    (net (code "282") (name "unconnected-(U$59-PadGND2)") (class "Default")
      (node (ref "U$59") (pin "GND2") (pinfunction "GND2_GND2") (pintype "bidirectional"))
    )
    (net (code "283") (name "unconnected-(U$59-PadGND3)") (class "Default")
      (node (ref "U$59") (pin "GND3") (pinfunction "GND3_GND3") (pintype "bidirectional"))
    )
    (net (code "284") (name "unconnected-(U$59-PadPROG)") (class "Default")
      (node (ref "U$59") (pin "PROG") (pinfunction "PROG_PROG") (pintype "bidirectional"))
    )
    (net (code "285") (name "unconnected-(U$59-PadRESET)") (class "Default")
      (node (ref "U$59") (pin "RESET") (pinfunction "RESET_RESET") (pintype "bidirectional"))
    )
    (net (code "286") (name "unconnected-(U$59-PadU5V)") (class "Default")
      (node (ref "U$59") (pin "U5V") (pinfunction "U5V_U5V") (pintype "bidirectional"))
    )
    (net (code "287") (name "unconnected-(U$59-PadUD+)") (class "Default")
      (node (ref "U$59") (pin "UD+") (pinfunction "UD+_UD+") (pintype "bidirectional"))
    )
    (net (code "288") (name "unconnected-(U$59-PadUD-)") (class "Default")
      (node (ref "U$59") (pin "UD-") (pinfunction "UD-_UD-") (pintype "bidirectional"))
    )
    (net (code "289") (name "unconnected-(U$59-PadUGND1)") (class "Default")
      (node (ref "U$59") (pin "UGND1") (pinfunction "UGND1_UGND1") (pintype "bidirectional"))
    )
    (net (code "290") (name "unconnected-(U$59-PadUGND2)") (class "Default")
      (node (ref "U$59") (pin "UGND2") (pinfunction "UGND2_UGND2") (pintype "bidirectional"))
    )
    (net (code "291") (name "unconnected-(U$59-PadVBAT)") (class "Default")
      (node (ref "U$59") (pin "VBAT") (pinfunction "VBAT_VBAT") (pintype "bidirectional"))
    )
    (net (code "292") (name "unconnected-(U$59-PadVUSB)") (class "Default")
      (node (ref "U$59") (pin "VUSB") (pinfunction "VUSB_VUSB") (pintype "bidirectional"))
    )
    (net (code "293") (name "unconnected-(U1-NC-Pad1)") (class "Default")
      (node (ref "U1") (pin "1") (pinfunction "NC_1") (pintype "no_connect"))
    )
    (net (code "294") (name "unconnected-(U1-NC_2-Pad20)") (class "Default")
      (node (ref "U1") (pin "20") (pinfunction "NC_2_20") (pintype "no_connect"))
    )
    (net (code "295") (name "unconnected-(U2-NC-Pad1)") (class "Default")
      (node (ref "U2") (pin "1") (pinfunction "NC_1") (pintype "no_connect"))
    )
    (net (code "296") (name "unconnected-(U2-NC_2-Pad20)") (class "Default")
      (node (ref "U2") (pin "20") (pinfunction "NC_2_20") (pintype "no_connect"))
    )
    (net (code "297") (name "unconnected-(U3-NC-Pad1)") (class "Default")
      (node (ref "U3") (pin "1") (pinfunction "NC_1") (pintype "no_connect"))
    )
    (net (code "298") (name "unconnected-(U3-NC_2-Pad20)") (class "Default")
      (node (ref "U3") (pin "20") (pinfunction "NC_2_20") (pintype "no_connect"))
    )
    (net (code "299") (name "unconnected-(U4-NC-Pad1)") (class "Default")
      (node (ref "U4") (pin "1") (pinfunction "NC_1") (pintype "no_connect"))
    )
    (net (code "300") (name "unconnected-(U4-NC_2-Pad20)") (class "Default")
      (node (ref "U4") (pin "20") (pinfunction "NC_2_20") (pintype "no_connect"))
    )
    (net (code "301") (name "unconnected-(U5-NC-Pad1)") (class "Default")
      (node (ref "U5") (pin "1") (pinfunction "NC_1") (pintype "no_connect"))
    )
    (net (code "302") (name "unconnected-(U5-NC_2-Pad20)") (class "Default")
      (node (ref "U5") (pin "20") (pinfunction "NC_2_20") (pintype "no_connect"))
    )
    (net (code "303") (name "unconnected-(U6-NC-Pad1)") (class "Default")
      (node (ref "U6") (pin "1") (pinfunction "NC_1") (pintype "no_connect"))
    )
    (net (code "304") (name "unconnected-(U6-NC_2-Pad20)") (class "Default")
      (node (ref "U6") (pin "20") (pinfunction "NC_2_20") (pintype "no_connect"))
    )
    (net (code "305") (name "unconnected-(U7-NC-Pad1)") (class "Default")
      (node (ref "U7") (pin "1") (pinfunction "NC_1") (pintype "no_connect"))
    )
    (net (code "306") (name "unconnected-(U7-NC_2-Pad20)") (class "Default")
      (node (ref "U7") (pin "20") (pinfunction "NC_2_20") (pintype "no_connect"))
    )
    (net (code "307") (name "unconnected-(U8-NC-Pad1)") (class "Default")
      (node (ref "U8") (pin "1") (pinfunction "NC_1") (pintype "no_connect"))
    )
    (net (code "308") (name "unconnected-(U8-NC_2-Pad20)") (class "Default")
      (node (ref "U8") (pin "20") (pinfunction "NC_2_20") (pintype "no_connect"))
    )
    (net (code "309") (name "unconnected-(U9-NC-Pad1)") (class "Default")
      (node (ref "U9") (pin "1") (pinfunction "NC_1") (pintype "no_connect"))
    )
    (net (code "310") (name "unconnected-(U9-NC_2-Pad20)") (class "Default")
      (node (ref "U9") (pin "20") (pinfunction "NC_2_20") (pintype "no_connect"))
    )
    (net (code "311") (name "unconnected-(U10-DRAIN5-Pad15)") (class "Default")
      (node (ref "U10") (pin "15") (pinfunction "DRAIN5_15") (pintype "output"))
    )
    (net (code "312") (name "unconnected-(U10-DRAIN6-Pad16)") (class "Default")
      (node (ref "U10") (pin "16") (pinfunction "DRAIN6_16") (pintype "output"))
    )
    (net (code "313") (name "unconnected-(U10-DRAIN7-Pad17)") (class "Default")
      (node (ref "U10") (pin "17") (pinfunction "DRAIN7_17") (pintype "output"))
    )
    (net (code "314") (name "unconnected-(U10-NC-Pad1)") (class "Default")
      (node (ref "U10") (pin "1") (pinfunction "NC_1") (pintype "no_connect"))
    )
    (net (code "315") (name "unconnected-(U10-NC_2-Pad20)") (class "Default")
      (node (ref "U10") (pin "20") (pinfunction "NC_2_20") (pintype "no_connect"))
    )
    (net (code "316") (name "unconnected-(U10-SER_OUT-Pad18)") (class "Default")
      (node (ref "U10") (pin "18") (pinfunction "SER_OUT_18") (pintype "output"))
    )
    (net (code "317") (name "unconnected-(U11-NC-Pad1)") (class "Default")
      (node (ref "U11") (pin "1") (pinfunction "NC_1") (pintype "no_connect"))
    )
    (net (code "318") (name "unconnected-(U11-NC_2-Pad20)") (class "Default")
      (node (ref "U11") (pin "20") (pinfunction "NC_2_20") (pintype "no_connect"))
    )
    (net (code "319") (name "unconnected-(U12-NC-Pad1)") (class "Default")
      (node (ref "U12") (pin "1") (pinfunction "NC_1") (pintype "no_connect"))
    )
    (net (code "320") (name "unconnected-(U12-NC_2-Pad20)") (class "Default")
      (node (ref "U12") (pin "20") (pinfunction "NC_2_20") (pintype "no_connect"))
    )
    (net (code "321") (name "unconnected-(U13-NC-Pad1)") (class "Default")
      (node (ref "U13") (pin "1") (pinfunction "NC_1") (pintype "no_connect"))
    )
    (net (code "322") (name "unconnected-(U13-NC_2-Pad20)") (class "Default")
      (node (ref "U13") (pin "20") (pinfunction "NC_2_20") (pintype "no_connect"))
    )
    (net (code "323") (name "unconnected-(U14-NC-Pad1)") (class "Default")
      (node (ref "U14") (pin "1") (pinfunction "NC_1") (pintype "no_connect"))
    )
    (net (code "324") (name "unconnected-(U14-NC_2-Pad20)") (class "Default")
      (node (ref "U14") (pin "20") (pinfunction "NC_2_20") (pintype "no_connect"))
    )
    (net (code "325") (name "unconnected-(U15-NC-Pad1)") (class "Default")
      (node (ref "U15") (pin "1") (pinfunction "NC_1") (pintype "no_connect"))
    )
    (net (code "326") (name "unconnected-(U15-NC_2-Pad20)") (class "Default")
      (node (ref "U15") (pin "20") (pinfunction "NC_2_20") (pintype "no_connect"))
    )
    (net (code "327") (name "unconnected-(U16-NC-Pad1)") (class "Default")
      (node (ref "U16") (pin "1") (pinfunction "NC_1") (pintype "no_connect"))
    )
    (net (code "328") (name "unconnected-(U16-NC_2-Pad20)") (class "Default")
      (node (ref "U16") (pin "20") (pinfunction "NC_2_20") (pintype "no_connect"))
    )
    (net (code "329") (name "unconnected-(U17-NC-Pad1)") (class "Default")
      (node (ref "U17") (pin "1") (pinfunction "NC_1") (pintype "no_connect"))
    )
    (net (code "330") (name "unconnected-(U17-NC_2-Pad20)") (class "Default")
      (node (ref "U17") (pin "20") (pinfunction "NC_2_20") (pintype "no_connect"))
    )
    (net (code "331") (name "unconnected-(U18-DRAIN5-Pad15)") (class "Default")
      (node (ref "U18") (pin "15") (pinfunction "DRAIN5_15") (pintype "output"))
    )
    (net (code "332") (name "unconnected-(U18-DRAIN6-Pad16)") (class "Default")
      (node (ref "U18") (pin "16") (pinfunction "DRAIN6_16") (pintype "output"))
    )
    (net (code "333") (name "unconnected-(U18-DRAIN7-Pad17)") (class "Default")
      (node (ref "U18") (pin "17") (pinfunction "DRAIN7_17") (pintype "output"))
    )
    (net (code "334") (name "unconnected-(U18-NC-Pad1)") (class "Default")
      (node (ref "U18") (pin "1") (pinfunction "NC_1") (pintype "no_connect"))
    )
    (net (code "335") (name "unconnected-(U18-NC_2-Pad20)") (class "Default")
      (node (ref "U18") (pin "20") (pinfunction "NC_2_20") (pintype "no_connect"))
    )
    (net (code "336") (name "unconnected-(U18-SER_OUT-Pad18)") (class "Default")
      (node (ref "U18") (pin "18") (pinfunction "SER_OUT_18") (pintype "output"))
    )
  )
)
